# audio-interface.net
KiCad netlist of a schematic drawn in EAGLE
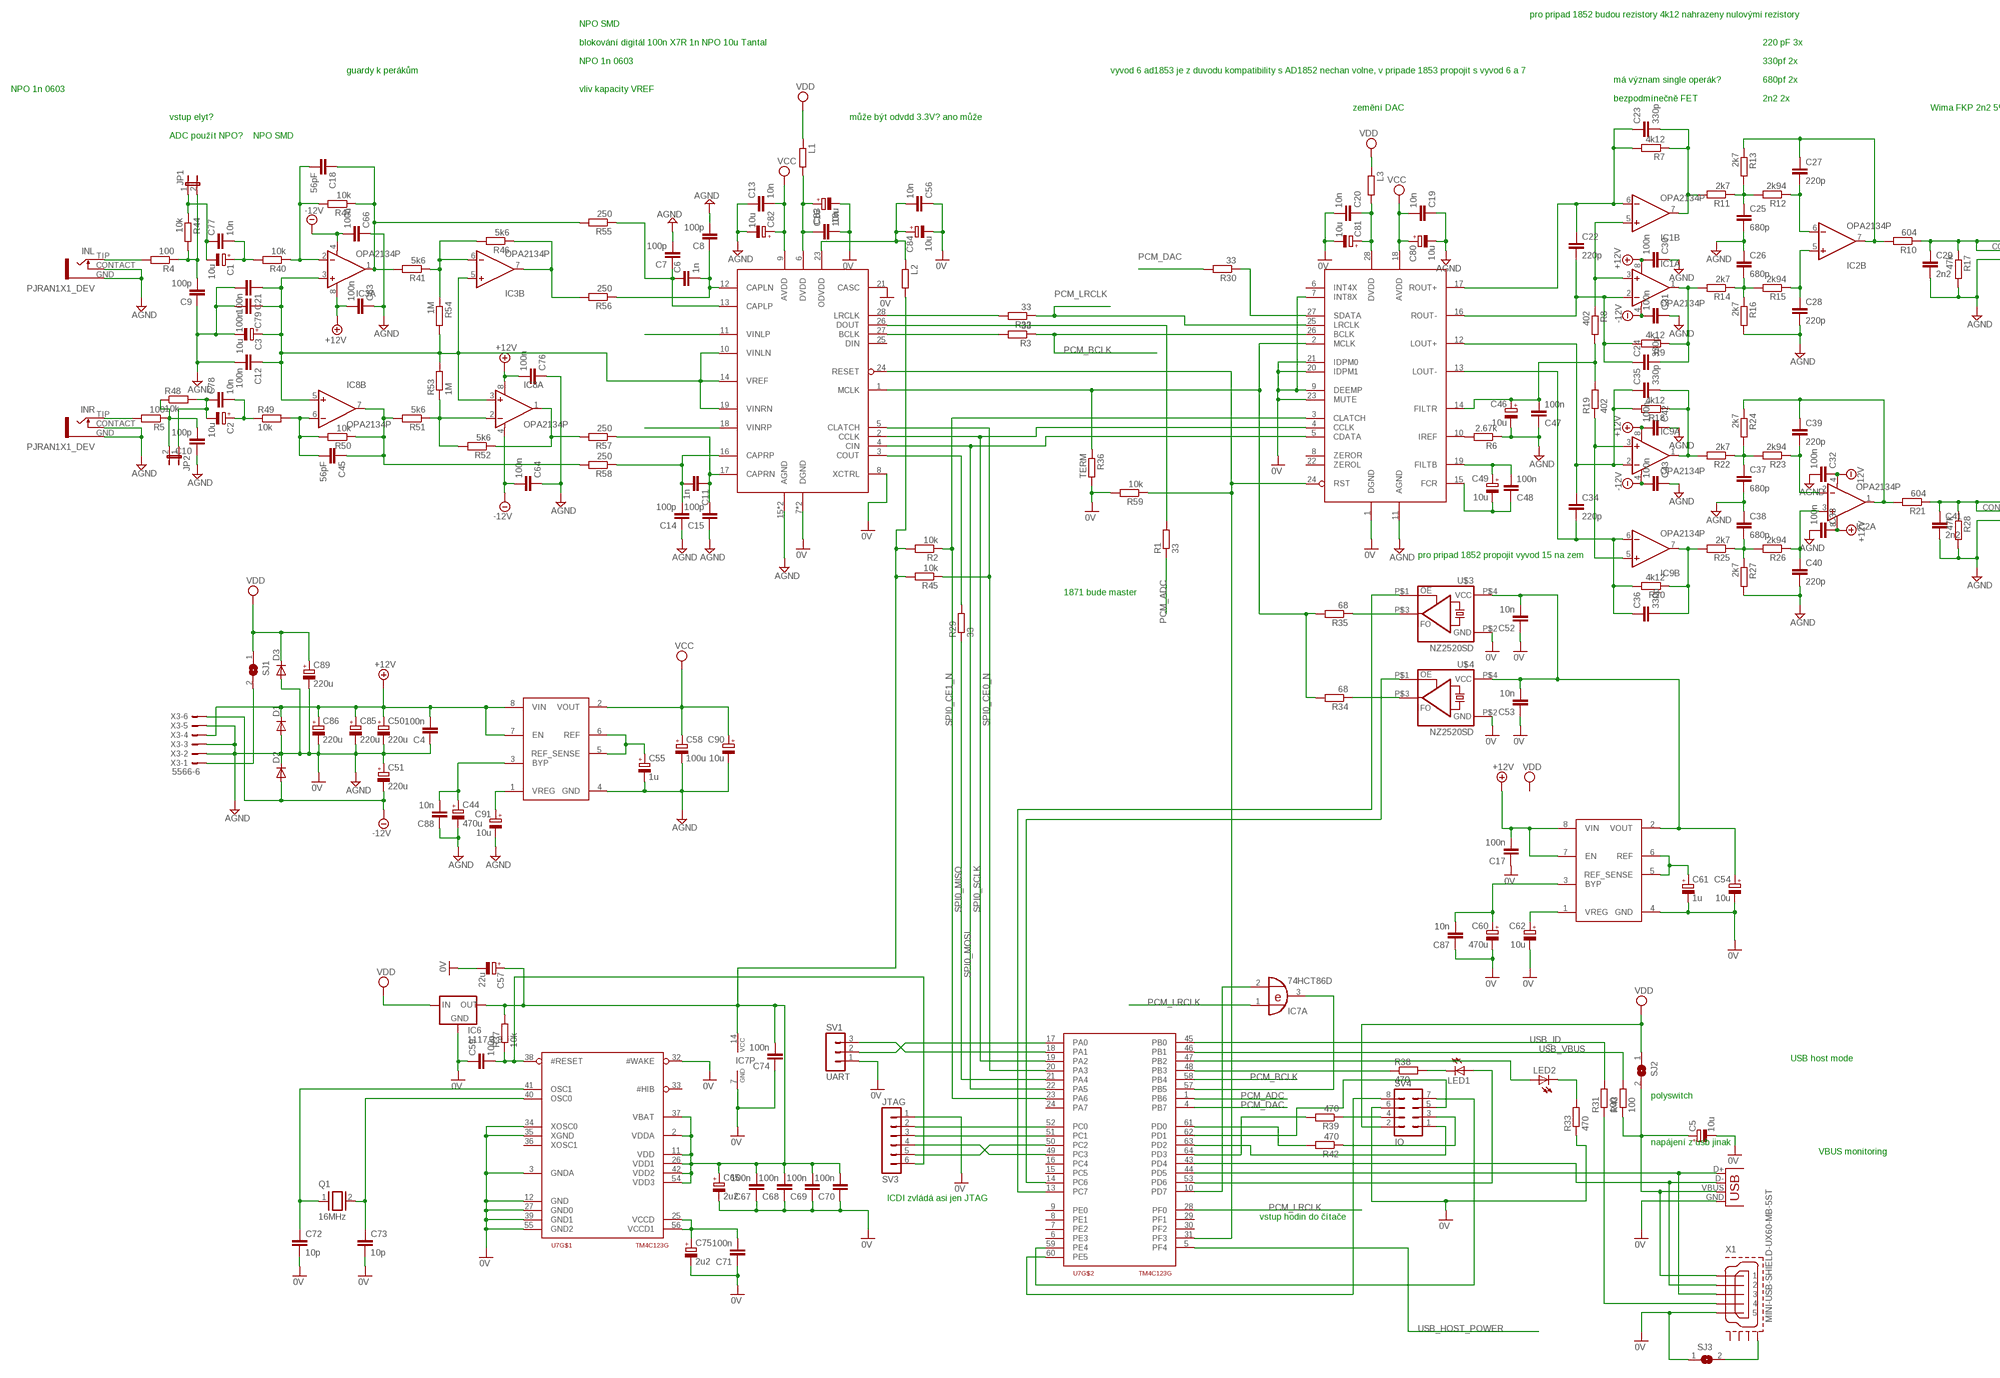
[diagram p0: schematic, sheet 1, part 1 of 2]
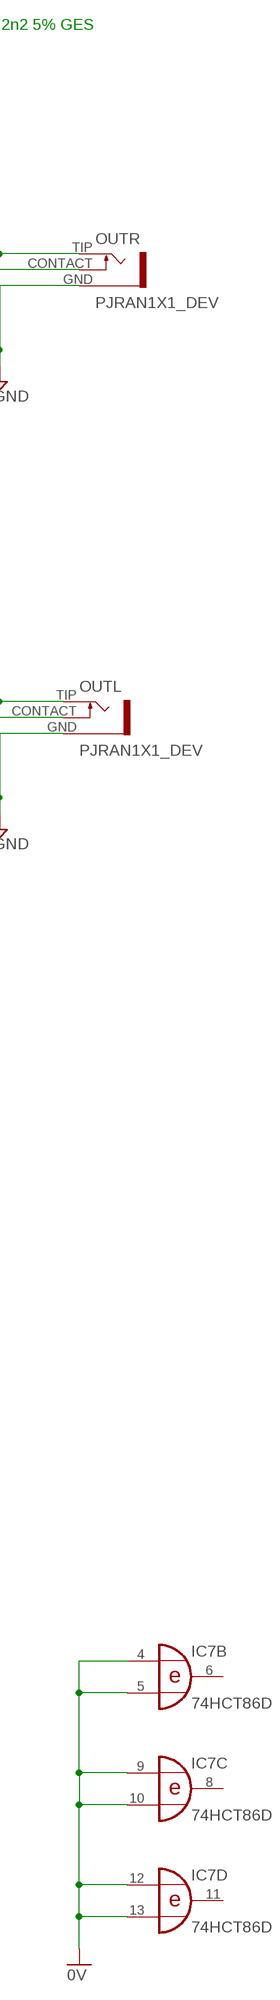
[diagram p1: schematic, sheet 1, part 2 of 2]

(export (version "E")
  (design (tool "Eeschema 10.0.6"))
  (components
    (comp (ref "C1")
      (value "10u")
      (footprint "eagle-import:E2,5-5")
      (libsource (lib "eagle-import") (part "CPOL-EUE2.5-5"))
    )
    (comp (ref "C2")
      (value "10u")
      (footprint "eagle-import:E2,5-5")
      (libsource (lib "eagle-import") (part "CPOL-EUE2.5-5"))
    )
    (comp (ref "C3")
      (value "10u")
      (footprint "eagle-import:E2,5-7")
      (libsource (lib "eagle-import") (part "CPOL-EUE2.5-7"))
    )
    (comp (ref "C4")
      (value "100n")
      (footprint "eagle-import:C0805")
      (libsource (lib "eagle-import") (part "C-EUC0805"))
    )
    (comp (ref "C5")
      (value "10u")
      (footprint "eagle-import:E2,5-7")
      (libsource (lib "eagle-import") (part "CPOL-EUE2.5-7"))
    )
    (comp (ref "C6")
      (value "1n")
      (footprint "eagle-import:C0805K")
      (libsource (lib "eagle-import") (part "C-EUC0805K"))
    )
    (comp (ref "C7")
      (value "100p")
      (footprint "eagle-import:C0805K")
      (libsource (lib "eagle-import") (part "C-EUC0805K"))
    )
    (comp (ref "C8")
      (value "100p")
      (footprint "eagle-import:C0805K")
      (libsource (lib "eagle-import") (part "C-EUC0805K"))
    )
    (comp (ref "C9")
      (value "100p")
      (footprint "eagle-import:C0805K")
      (libsource (lib "eagle-import") (part "C-EUC0805K"))
    )
    (comp (ref "C10")
      (value "100p")
      (footprint "eagle-import:C0805K")
      (libsource (lib "eagle-import") (part "C-EUC0805K"))
    )
    (comp (ref "C11")
      (value "1n")
      (footprint "eagle-import:C0805K")
      (libsource (lib "eagle-import") (part "C-EUC0805K"))
    )
    (comp (ref "C12")
      (value "100n")
      (footprint "eagle-import:C0805")
      (libsource (lib "eagle-import") (part "C-EUC0805"))
    )
    (comp (ref "C13")
      (value "10n")
      (footprint "eagle-import:C0805")
      (libsource (lib "eagle-import") (part "C-EUC0805"))
    )
    (comp (ref "C14")
      (value "100p")
      (footprint "eagle-import:C0805K")
      (libsource (lib "eagle-import") (part "C-EUC0805K"))
    )
    (comp (ref "C15")
      (value "100p")
      (footprint "eagle-import:C0805K")
      (libsource (lib "eagle-import") (part "C-EUC0805K"))
    )
    (comp (ref "C16")
      (value "10n")
      (footprint "eagle-import:C0805")
      (libsource (lib "eagle-import") (part "C-EUC0805"))
    )
    (comp (ref "C17")
      (value "100n")
      (footprint "eagle-import:C0805")
      (libsource (lib "eagle-import") (part "C-EUC0805"))
    )
    (comp (ref "C18")
      (value "56pF")
      (footprint "eagle-import:C0805K")
      (libsource (lib "eagle-import") (part "C-EUC0805K"))
    )
    (comp (ref "C19")
      (value "10n")
      (footprint "eagle-import:C0805")
      (libsource (lib "eagle-import") (part "C-EUC0805"))
    )
    (comp (ref "C20")
      (value "10n")
      (footprint "eagle-import:C0805")
      (libsource (lib "eagle-import") (part "C-EUC0805"))
    )
    (comp (ref "C21")
      (value "100n")
      (footprint "eagle-import:C0805")
      (libsource (lib "eagle-import") (part "C-EUC0805"))
    )
    (comp (ref "C22")
      (value "220p")
      (footprint "eagle-import:C0805K")
      (libsource (lib "eagle-import") (part "C-EUC0805K"))
    )
    (comp (ref "C23")
      (value "330p")
      (footprint "eagle-import:C0805K")
      (libsource (lib "eagle-import") (part "C-EUC0805K"))
    )
    (comp (ref "C24")
      (value "330p")
      (footprint "eagle-import:C0805K")
      (libsource (lib "eagle-import") (part "C-EUC0805K"))
    )
    (comp (ref "C25")
      (value "680p")
      (footprint "eagle-import:C050-050X075")
      (libsource (lib "eagle-import") (part "C-EU050-050X075"))
    )
    (comp (ref "C26")
      (value "680p")
      (footprint "eagle-import:C050-050X075")
      (libsource (lib "eagle-import") (part "C-EU050-050X075"))
    )
    (comp (ref "C27")
      (value "220p")
      (footprint "eagle-import:C0805K")
      (libsource (lib "eagle-import") (part "C-EUC0805K"))
    )
    (comp (ref "C28")
      (value "220p")
      (footprint "eagle-import:C0805K")
      (libsource (lib "eagle-import") (part "C-EUC0805K"))
    )
    (comp (ref "C29")
      (value "2n2")
      (footprint "eagle-import:C050-050X075")
      (libsource (lib "eagle-import") (part "C-EU050-050X075"))
    )
    (comp (ref "C30")
      (value "100n")
      (footprint "eagle-import:C0805")
      (libsource (lib "eagle-import") (part "C-EUC0805"))
    )
    (comp (ref "C31")
      (value "100n")
      (footprint "eagle-import:C0805")
      (libsource (lib "eagle-import") (part "C-EUC0805"))
    )
    (comp (ref "C32")
      (value "100n")
      (footprint "eagle-import:C0805")
      (libsource (lib "eagle-import") (part "C-EUC0805"))
    )
    (comp (ref "C33")
      (value "100n")
      (footprint "eagle-import:C0805")
      (libsource (lib "eagle-import") (part "C-EUC0805"))
    )
    (comp (ref "C34")
      (value "220p")
      (footprint "eagle-import:C0805K")
      (libsource (lib "eagle-import") (part "C-EUC0805K"))
    )
    (comp (ref "C35")
      (value "330p")
      (footprint "eagle-import:C0805K")
      (libsource (lib "eagle-import") (part "C-EUC0805K"))
    )
    (comp (ref "C36")
      (value "330p")
      (footprint "eagle-import:C0805K")
      (libsource (lib "eagle-import") (part "C-EUC0805K"))
    )
    (comp (ref "C37")
      (value "680p")
      (footprint "eagle-import:C050-050X075")
      (libsource (lib "eagle-import") (part "C-EU050-050X075"))
    )
    (comp (ref "C38")
      (value "680p")
      (footprint "eagle-import:C050-050X075")
      (libsource (lib "eagle-import") (part "C-EU050-050X075"))
    )
    (comp (ref "C39")
      (value "220p")
      (footprint "eagle-import:C0805K")
      (libsource (lib "eagle-import") (part "C-EUC0805K"))
    )
    (comp (ref "C40")
      (value "220p")
      (footprint "eagle-import:C0805K")
      (libsource (lib "eagle-import") (part "C-EUC0805K"))
    )
    (comp (ref "C41")
      (value "2n2")
      (footprint "eagle-import:C050-050X075")
      (libsource (lib "eagle-import") (part "C-EU050-050X075"))
    )
    (comp (ref "C42")
      (value "100n")
      (footprint "eagle-import:C0805")
      (libsource (lib "eagle-import") (part "C-EUC0805"))
    )
    (comp (ref "C43")
      (value "100n")
      (footprint "eagle-import:C0805")
      (libsource (lib "eagle-import") (part "C-EUC0805"))
    )
    (comp (ref "C44")
      (value "470u")
      (footprint "eagle-import:E2,5-7")
      (libsource (lib "eagle-import") (part "CPOL-EUE2.5-7"))
    )
    (comp (ref "C45")
      (value "56pF")
      (footprint "eagle-import:C0805K")
      (libsource (lib "eagle-import") (part "C-EUC0805K"))
    )
    (comp (ref "C46")
      (value "10u")
      (footprint "eagle-import:SMC_A")
      (libsource (lib "eagle-import") (part "CPOL-EUSMCA"))
    )
    (comp (ref "C47")
      (value "100n")
      (footprint "eagle-import:C0805")
      (libsource (lib "eagle-import") (part "C-EUC0805"))
    )
    (comp (ref "C48")
      (value "100n")
      (footprint "eagle-import:C0805")
      (libsource (lib "eagle-import") (part "C-EUC0805"))
    )
    (comp (ref "C49")
      (value "10u")
      (footprint "eagle-import:SMC_A")
      (libsource (lib "eagle-import") (part "CPOL-EUSMCA"))
    )
    (comp (ref "C50")
      (value "220u")
      (footprint "eagle-import:E2,5-7")
      (libsource (lib "eagle-import") (part "CPOL-EUE2.5-7"))
    )
    (comp (ref "C51")
      (value "220u")
      (footprint "eagle-import:E2,5-7")
      (libsource (lib "eagle-import") (part "CPOL-EUE2.5-7"))
    )
    (comp (ref "C52")
      (value "10n")
      (footprint "eagle-import:C0805")
      (libsource (lib "eagle-import") (part "C-EUC0805"))
    )
    (comp (ref "C53")
      (value "10n")
      (footprint "eagle-import:C0805")
      (libsource (lib "eagle-import") (part "C-EUC0805"))
    )
    (comp (ref "C54")
      (value "10u")
      (footprint "eagle-import:CT6032")
      (libsource (lib "eagle-import") (part "CPOL-EUCT6032"))
    )
    (comp (ref "C55")
      (value "1u")
      (footprint "eagle-import:CT3216")
      (libsource (lib "eagle-import") (part "CPOL-EUCT3216"))
    )
    (comp (ref "C56")
      (value "10n")
      (footprint "eagle-import:C0805")
      (libsource (lib "eagle-import") (part "C-EUC0805"))
    )
    (comp (ref "C57")
      (value "22u")
      (footprint "eagle-import:CT6032")
      (libsource (lib "eagle-import") (part "CPOL-EUCT6032"))
    )
    (comp (ref "C58")
      (value "100u")
      (footprint "eagle-import:E2,5-7")
      (libsource (lib "eagle-import") (part "CPOL-EUE2.5-7"))
    )
    (comp (ref "C59")
      (value "100n")
      (footprint "eagle-import:C0805")
      (libsource (lib "eagle-import") (part "C-EUC0805"))
    )
    (comp (ref "C60")
      (value "470u")
      (footprint "eagle-import:E2,5-7")
      (libsource (lib "eagle-import") (part "CPOL-EUE2.5-7"))
    )
    (comp (ref "C61")
      (value "1u")
      (footprint "eagle-import:CT3216")
      (libsource (lib "eagle-import") (part "CPOL-EUCT3216"))
    )
    (comp (ref "C62")
      (value "10u")
      (footprint "eagle-import:CT6032")
      (libsource (lib "eagle-import") (part "CPOL-EUCT6032"))
    )
    (comp (ref "C63")
      (value "100n")
      (footprint "eagle-import:C0805")
      (libsource (lib "eagle-import") (part "C-EUC0805"))
    )
    (comp (ref "C64")
      (value "100n")
      (footprint "eagle-import:C0805")
      (libsource (lib "eagle-import") (part "C-EUC0805"))
    )
    (comp (ref "C65")
      (value "2u2")
      (footprint "eagle-import:CT3216")
      (libsource (lib "eagle-import") (part "CPOL-EUCT3216"))
    )
    (comp (ref "C66")
      (value "100n")
      (footprint "eagle-import:C0805")
      (libsource (lib "eagle-import") (part "C-EUC0805"))
    )
    (comp (ref "C67")
      (value "100n")
      (footprint "eagle-import:C0805")
      (libsource (lib "eagle-import") (part "C-EUC0805"))
    )
    (comp (ref "C68")
      (value "100n")
      (footprint "eagle-import:C0805")
      (libsource (lib "eagle-import") (part "C-EUC0805"))
    )
    (comp (ref "C69")
      (value "100n")
      (footprint "eagle-import:C0805")
      (libsource (lib "eagle-import") (part "C-EUC0805"))
    )
    (comp (ref "C70")
      (value "100n")
      (footprint "eagle-import:C0805")
      (libsource (lib "eagle-import") (part "C-EUC0805"))
    )
    (comp (ref "C71")
      (value "100n")
      (footprint "eagle-import:C0805")
      (libsource (lib "eagle-import") (part "C-EUC0805"))
    )
    (comp (ref "C72")
      (value "10p")
      (footprint "eagle-import:C0805")
      (libsource (lib "eagle-import") (part "C-EUC0805"))
    )
    (comp (ref "C73")
      (value "10p")
      (footprint "eagle-import:C0805")
      (libsource (lib "eagle-import") (part "C-EUC0805"))
    )
    (comp (ref "C74")
      (value "100n")
      (footprint "eagle-import:C0805")
      (libsource (lib "eagle-import") (part "C-EUC0805"))
    )
    (comp (ref "C75")
      (value "2u2")
      (footprint "eagle-import:CT3216")
      (libsource (lib "eagle-import") (part "CPOL-EUCT3216"))
    )
    (comp (ref "C76")
      (value "100n")
      (footprint "eagle-import:C0805")
      (libsource (lib "eagle-import") (part "C-EUC0805"))
    )
    (comp (ref "C77")
      (value "10n")
      (footprint "eagle-import:C0805K")
      (libsource (lib "eagle-import") (part "C-EUC0805K"))
    )
    (comp (ref "C78")
      (value "10n")
      (footprint "eagle-import:C0805K")
      (libsource (lib "eagle-import") (part "C-EUC0805K"))
    )
    (comp (ref "C79")
      (value "100n")
      (footprint "eagle-import:C0805")
      (libsource (lib "eagle-import") (part "C-EUC0805"))
    )
    (comp (ref "C80")
      (value "10u")
      (footprint "eagle-import:SMC_A")
      (libsource (lib "eagle-import") (part "CPOL-EUSMCA"))
    )
    (comp (ref "C81")
      (value "10u")
      (footprint "eagle-import:SMC_A")
      (libsource (lib "eagle-import") (part "CPOL-EUSMCA"))
    )
    (comp (ref "C82")
      (value "10u")
      (footprint "eagle-import:SMC_A")
      (libsource (lib "eagle-import") (part "CPOL-EUSMCA"))
    )
    (comp (ref "C83")
      (value "10u")
      (footprint "eagle-import:SMC_A")
      (libsource (lib "eagle-import") (part "CPOL-EUSMCA"))
    )
    (comp (ref "C84")
      (value "10u")
      (footprint "eagle-import:SMC_A")
      (libsource (lib "eagle-import") (part "CPOL-EUSMCA"))
    )
    (comp (ref "C85")
      (value "220u")
      (footprint "eagle-import:E2,5-7")
      (libsource (lib "eagle-import") (part "CPOL-EUE2.5-7"))
    )
    (comp (ref "C86")
      (value "220u")
      (footprint "eagle-import:E2,5-7")
      (libsource (lib "eagle-import") (part "CPOL-EUE2.5-7"))
    )
    (comp (ref "C87")
      (value "10n")
      (footprint "eagle-import:C0805")
      (libsource (lib "eagle-import") (part "C-EUC0805"))
    )
    (comp (ref "C88")
      (value "10n")
      (footprint "eagle-import:C0805")
      (libsource (lib "eagle-import") (part "C-EUC0805"))
    )
    (comp (ref "C89")
      (value "220u")
      (footprint "eagle-import:E2,5-7")
      (libsource (lib "eagle-import") (part "CPOL-EUE2.5-7"))
    )
    (comp (ref "C90")
      (value "10u")
      (footprint "eagle-import:CT6032")
      (libsource (lib "eagle-import") (part "CPOL-EUCT6032"))
    )
    (comp (ref "C91")
      (value "10u")
      (footprint "eagle-import:CT6032")
      (libsource (lib "eagle-import") (part "CPOL-EUCT6032"))
    )
    (comp (ref "D1")
      (value "DIODE-MINIMELF")
      (footprint "eagle-import:MINIMELF")
      (libsource (lib "eagle-import") (part "DIODE-MINIMELF"))
    )
    (comp (ref "D2")
      (value "DIODE-MINIMELF")
      (footprint "eagle-import:MINIMELF")
      (libsource (lib "eagle-import") (part "DIODE-MINIMELF"))
    )
    (comp (ref "D3")
      (value "DIODE-MINIMELF")
      (footprint "eagle-import:MINIMELF")
      (libsource (lib "eagle-import") (part "DIODE-MINIMELF"))
    )
    (comp (ref "IC1")
      (value "OPA2134P")
      (footprint "eagle-import:DIL08")
      (fields
        (field (name "MF") "TEXAS INSTRUMENTS")
        (field (name "MPN") "OPA2134PA")
        (field (name "MF_1") "TEXAS INSTRUMENTS")
        (field (name "MPN_1") "OPA2134PA")
        (field (name "OC_FARNELL") "1097574")
        (field (name "OC_NEWARK") "74K3897")
      )
      (libsource (lib "eagle-import") (part "OPA2134P"))
    )
    (comp (ref "IC2")
      (value "OPA2134P")
      (footprint "eagle-import:DIL08")
      (fields (field (name "MF") "TEXAS INSTRUMENTS") (field (name "MPN") "OPA2134PA"))
      (libsource (lib "eagle-import") (part "OPA2134P"))
    )
    (comp (ref "IC3")
      (value "OPA2134P")
      (footprint "eagle-import:DIL08")
      (fields
        (field (name "MF") "TEXAS INSTRUMENTS")
        (field (name "MPN") "OPA2134PA")
        (field (name "MF_1") "TEXAS INSTRUMENTS")
        (field (name "MPN_1") "OPA2134PA")
        (field (name "OC_FARNELL") "1097574")
        (field (name "OC_NEWARK") "74K3897")
      )
      (libsource (lib "eagle-import") (part "OPA2134P"))
    )
    (comp (ref "IC6")
      (value "1117 3.3")
      (footprint "eagle-import:SOT223")
      (libsource (lib "eagle-import") (part "LM1117"))
    )
    (comp (ref "IC7")
      (value "74HCT86D")
      (footprint "eagle-import:SO14")
      (libsource (lib "eagle-import") (part "7486DHCT"))
    )
    (comp (ref "IC8")
      (value "OPA2134P")
      (footprint "eagle-import:DIL08")
      (fields
        (field (name "MF") "TEXAS INSTRUMENTS")
        (field (name "MPN") "OPA2134PA")
        (field (name "MF_1") "TEXAS INSTRUMENTS")
        (field (name "MPN_1") "OPA2134PA")
        (field (name "OC_FARNELL") "1097574")
        (field (name "OC_NEWARK") "74K3897")
      )
      (libsource (lib "eagle-import") (part "OPA2134P"))
    )
    (comp (ref "IC9")
      (value "OPA2134P")
      (footprint "eagle-import:DIL08")
      (fields
        (field (name "MF") "TEXAS INSTRUMENTS")
        (field (name "MPN") "OPA2134PA")
        (field (name "MF_1") "TEXAS INSTRUMENTS")
        (field (name "MPN_1") "OPA2134PA")
        (field (name "OC_FARNELL") "1097574")
        (field (name "OC_NEWARK") "74K3897")
      )
      (libsource (lib "eagle-import") (part "OPA2134P"))
    )
    (comp (ref "INL")
      (value "PJRAN1X1_DEV")
      (footprint "eagle-import:PJRAN1X1")
      (libsource (lib "eagle-import") (part "PJRAN1X1_DEV"))
    )
    (comp (ref "INR")
      (value "PJRAN1X1_DEV")
      (footprint "eagle-import:PJRAN1X1")
      (libsource (lib "eagle-import") (part "PJRAN1X1_DEV"))
    )
    (comp (ref "JP1")
      (value "JP1E")
      (footprint "eagle-import:JP1")
      (libsource (lib "eagle-import") (part "JP1E"))
    )
    (comp (ref "JP2")
      (value "JP1E")
      (footprint "eagle-import:JP1")
      (libsource (lib "eagle-import") (part "JP1E"))
    )
    (comp (ref "L1")
      (value "R-EU_R0805")
      (footprint "eagle-import:R0805")
      (libsource (lib "eagle-import") (part "R-EU_R0805"))
    )
    (comp (ref "L2")
      (value "R-EU_R0805")
      (footprint "eagle-import:R0805")
      (libsource (lib "eagle-import") (part "R-EU_R0805"))
    )
    (comp (ref "L3")
      (value "R-EU_R0805")
      (footprint "eagle-import:R0805")
      (libsource (lib "eagle-import") (part "R-EU_R0805"))
    )
    (comp (ref "LED1")
      (value "LED3MM")
      (footprint "eagle-import:LED3MM")
      (libsource (lib "eagle-import") (part "LED3MM"))
    )
    (comp (ref "LED2")
      (value "LED3MM")
      (footprint "eagle-import:LED3MM")
      (libsource (lib "eagle-import") (part "LED3MM"))
    )
    (comp (ref "OUTL")
      (value "PJRAN1X1_DEV")
      (footprint "eagle-import:PJRAN1X1")
      (libsource (lib "eagle-import") (part "PJRAN1X1_DEV"))
    )
    (comp (ref "OUTR")
      (value "PJRAN1X1_DEV")
      (footprint "eagle-import:PJRAN1X1")
      (libsource (lib "eagle-import") (part "PJRAN1X1_DEV"))
    )
    (comp (ref "Q1")
      (value "16MHz")
      (footprint "eagle-import:QS")
      (libsource (lib "eagle-import") (part "XTAL/S"))
    )
    (comp (ref "R1")
      (value "33")
      (footprint "eagle-import:R0805")
      (libsource (lib "eagle-import") (part "R-EU_R0805"))
    )
    (comp (ref "R2")
      (value "10k")
      (footprint "eagle-import:R0805")
      (libsource (lib "eagle-import") (part "R-EU_R0805"))
    )
    (comp (ref "R3")
      (value "33")
      (footprint "eagle-import:R0805")
      (libsource (lib "eagle-import") (part "R-EU_R0805"))
    )
    (comp (ref "R4")
      (value "100")
      (footprint "eagle-import:M0805")
      (libsource (lib "eagle-import") (part "R-EU_M0805"))
    )
    (comp (ref "R5")
      (value "100")
      (footprint "eagle-import:M0805")
      (libsource (lib "eagle-import") (part "R-EU_M0805"))
    )
    (comp (ref "R6")
      (value "2.67k")
      (footprint "eagle-import:M1406")
      (libsource (lib "eagle-import") (part "R-EU_M1406"))
    )
    (comp (ref "R7")
      (value "4k12")
      (footprint "eagle-import:M1206")
      (libsource (lib "eagle-import") (part "R-EU_M1206"))
    )
    (comp (ref "R8")
      (value "402")
      (footprint "eagle-import:M1206")
      (libsource (lib "eagle-import") (part "R-EU_M1206"))
    )
    (comp (ref "R9")
      (value "4k12")
      (footprint "eagle-import:M1206")
      (libsource (lib "eagle-import") (part "R-EU_M1206"))
    )
    (comp (ref "R10")
      (value "604")
      (footprint "eagle-import:M1206")
      (libsource (lib "eagle-import") (part "R-EU_M1206"))
    )
    (comp (ref "R11")
      (value "2k7")
      (footprint "eagle-import:M1206")
      (libsource (lib "eagle-import") (part "R-EU_M1206"))
    )
    (comp (ref "R12")
      (value "2k94")
      (footprint "eagle-import:M1206")
      (libsource (lib "eagle-import") (part "R-EU_M1206"))
    )
    (comp (ref "R13")
      (value "2k7")
      (footprint "eagle-import:M1206")
      (libsource (lib "eagle-import") (part "R-EU_M1206"))
    )
    (comp (ref "R14")
      (value "2k7")
      (footprint "eagle-import:M1206")
      (libsource (lib "eagle-import") (part "R-EU_M1206"))
    )
    (comp (ref "R15")
      (value "2k94")
      (footprint "eagle-import:M1206")
      (libsource (lib "eagle-import") (part "R-EU_M1206"))
    )
    (comp (ref "R16")
      (value "2k7")
      (footprint "eagle-import:M1206")
      (libsource (lib "eagle-import") (part "R-EU_M1206"))
    )
    (comp (ref "R17")
      (value "47k")
      (footprint "eagle-import:M1206")
      (libsource (lib "eagle-import") (part "R-EU_M1206"))
    )
    (comp (ref "R18")
      (value "4k12")
      (footprint "eagle-import:M1206")
      (libsource (lib "eagle-import") (part "R-EU_M1206"))
    )
    (comp (ref "R19")
      (value "402")
      (footprint "eagle-import:M1206")
      (libsource (lib "eagle-import") (part "R-EU_M1206"))
    )
    (comp (ref "R20")
      (value "4k12")
      (footprint "eagle-import:M1206")
      (libsource (lib "eagle-import") (part "R-EU_M1206"))
    )
    (comp (ref "R21")
      (value "604")
      (footprint "eagle-import:M1206")
      (libsource (lib "eagle-import") (part "R-EU_M1206"))
    )
    (comp (ref "R22")
      (value "2k7")
      (footprint "eagle-import:M1206")
      (libsource (lib "eagle-import") (part "R-EU_M1206"))
    )
    (comp (ref "R23")
      (value "2k94")
      (footprint "eagle-import:M1206")
      (libsource (lib "eagle-import") (part "R-EU_M1206"))
    )
    (comp (ref "R24")
      (value "2k7")
      (footprint "eagle-import:M1206")
      (libsource (lib "eagle-import") (part "R-EU_M1206"))
    )
    (comp (ref "R25")
      (value "2k7")
      (footprint "eagle-import:M1206")
      (libsource (lib "eagle-import") (part "R-EU_M1206"))
    )
    (comp (ref "R26")
      (value "2k94")
      (footprint "eagle-import:M1206")
      (libsource (lib "eagle-import") (part "R-EU_M1206"))
    )
    (comp (ref "R27")
      (value "2k7")
      (footprint "eagle-import:M1206")
      (libsource (lib "eagle-import") (part "R-EU_M1206"))
    )
    (comp (ref "R28")
      (value "47k")
      (footprint "eagle-import:M1206")
      (libsource (lib "eagle-import") (part "R-EU_M1206"))
    )
    (comp (ref "R29")
      (value "33")
      (footprint "eagle-import:R0805")
      (libsource (lib "eagle-import") (part "R-EU_R0805"))
    )
    (comp (ref "R30")
      (value "33")
      (footprint "eagle-import:R0805")
      (libsource (lib "eagle-import") (part "R-EU_R0805"))
    )
    (comp (ref "R31")
      (value "100")
      (footprint "eagle-import:R0805")
      (libsource (lib "eagle-import") (part "R-EU_R0805"))
    )
    (comp (ref "R32")
      (value "33")
      (footprint "eagle-import:R0805")
      (libsource (lib "eagle-import") (part "R-EU_R0805"))
    )
    (comp (ref "R33")
      (value "470")
      (footprint "eagle-import:R0805")
      (libsource (lib "eagle-import") (part "R-EU_R0805"))
    )
    (comp (ref "R34")
      (value "68")
      (footprint "eagle-import:M1206")
      (libsource (lib "eagle-import") (part "R-EU_M1206"))
    )
    (comp (ref "R35")
      (value "68")
      (footprint "eagle-import:M1206")
      (libsource (lib "eagle-import") (part "R-EU_M1206"))
    )
    (comp (ref "R36")
      (value "TERM")
      (footprint "eagle-import:R0805")
      (libsource (lib "eagle-import") (part "R-EU_R0805"))
    )
    (comp (ref "R37")
      (value "10k")
      (footprint "eagle-import:R0805")
      (libsource (lib "eagle-import") (part "R-EU_R0805"))
    )
    (comp (ref "R38")
      (value "470")
      (footprint "eagle-import:R0805")
      (libsource (lib "eagle-import") (part "R-EU_R0805"))
    )
    (comp (ref "R39")
      (value "470")
      (footprint "eagle-import:R0805")
      (libsource (lib "eagle-import") (part "R-EU_R0805"))
    )
    (comp (ref "R40")
      (value "10k")
      (footprint "eagle-import:M1206")
      (libsource (lib "eagle-import") (part "R-EU_M1206"))
    )
    (comp (ref "R41")
      (value "5k6")
      (footprint "eagle-import:M1206")
      (libsource (lib "eagle-import") (part "R-EU_M1206"))
    )
    (comp (ref "R42")
      (value "470")
      (footprint "eagle-import:R0805")
      (libsource (lib "eagle-import") (part "R-EU_R0805"))
    )
    (comp (ref "R43")
      (value "100")
      (footprint "eagle-import:R0805")
      (libsource (lib "eagle-import") (part "R-EU_R0805"))
    )
    (comp (ref "R44")
      (value "10k")
      (footprint "eagle-import:M1206")
      (libsource (lib "eagle-import") (part "R-EU_M1206"))
    )
    (comp (ref "R45")
      (value "10k")
      (footprint "eagle-import:R0805")
      (libsource (lib "eagle-import") (part "R-EU_R0805"))
    )
    (comp (ref "R46")
      (value "5k6")
      (footprint "eagle-import:M1206")
      (libsource (lib "eagle-import") (part "R-EU_M1206"))
    )
    (comp (ref "R47")
      (value "10k")
      (footprint "eagle-import:M1206")
      (libsource (lib "eagle-import") (part "R-EU_M1206"))
    )
    (comp (ref "R48")
      (value "10k")
      (footprint "eagle-import:M1206")
      (libsource (lib "eagle-import") (part "R-EU_M1206"))
    )
    (comp (ref "R49")
      (value "10k")
      (footprint "eagle-import:M1206")
      (libsource (lib "eagle-import") (part "R-EU_M1206"))
    )
    (comp (ref "R50")
      (value "10k")
      (footprint "eagle-import:M1206")
      (libsource (lib "eagle-import") (part "R-EU_M1206"))
    )
    (comp (ref "R51")
      (value "5k6")
      (footprint "eagle-import:M1206")
      (libsource (lib "eagle-import") (part "R-EU_M1206"))
    )
    (comp (ref "R52")
      (value "5k6")
      (footprint "eagle-import:M1206")
      (libsource (lib "eagle-import") (part "R-EU_M1206"))
    )
    (comp (ref "R53")
      (value "1M")
      (footprint "eagle-import:M1206")
      (libsource (lib "eagle-import") (part "R-EU_M1206"))
    )
    (comp (ref "R54")
      (value "1M")
      (footprint "eagle-import:M1206")
      (libsource (lib "eagle-import") (part "R-EU_M1206"))
    )
    (comp (ref "R55")
      (value "250")
      (footprint "eagle-import:M1206")
      (libsource (lib "eagle-import") (part "R-EU_M1206"))
    )
    (comp (ref "R56")
      (value "250")
      (footprint "eagle-import:M1206")
      (libsource (lib "eagle-import") (part "R-EU_M1206"))
    )
    (comp (ref "R57")
      (value "250")
      (footprint "eagle-import:M1206")
      (libsource (lib "eagle-import") (part "R-EU_M1206"))
    )
    (comp (ref "R58")
      (value "250")
      (footprint "eagle-import:M1206")
      (libsource (lib "eagle-import") (part "R-EU_M1206"))
    )
    (comp (ref "R59")
      (value "10k")
      (footprint "eagle-import:R0805")
      (libsource (lib "eagle-import") (part "R-EU_R0805"))
    )
    (comp (ref "SJ1") (value "SJ") (footprint "eagle-import:SJ") (libsource (lib "eagle-import") (part "SJ")))
    (comp (ref "SJ2") (value "SJ") (footprint "eagle-import:SJ") (libsource (lib "eagle-import") (part "SJ")))
    (comp (ref "SJ3") (value "SJ") (footprint "eagle-import:SJ") (libsource (lib "eagle-import") (part "SJ")))
    (comp (ref "SV1")
      (value "UART")
      (footprint "eagle-import:MA03-1")
      (libsource (lib "eagle-import") (part "MA03-1"))
    )
    (comp (ref "SV3")
      (value "JTAG")
      (footprint "eagle-import:MA06-1")
      (libsource (lib "eagle-import") (part "MA06-1"))
    )
    (comp (ref "SV4")
      (value "IO")
      (footprint "eagle-import:MA04-2")
      (libsource (lib "eagle-import") (part "MA04-2"))
    )
    (comp (ref "U$3")
      (value "NZ2520SD")
      (footprint "eagle-import:OSC2X2.5")
      (libsource (lib "eagle-import") (part "OSC-3ST"))
    )
    (comp (ref "U$4")
      (value "NZ2520SD")
      (footprint "eagle-import:OSC2X2.5")
      (libsource (lib "eagle-import") (part "OSC-3ST"))
    )
    (comp (ref "U1")
      (value "AD1853")
      (footprint "eagle-import:SSOP-28")
      (libsource (lib "eagle-import") (part "AD1853"))
    )
    (comp (ref "U2")
      (value "AD1871")
      (footprint "eagle-import:SSOP-28")
      (libsource (lib "eagle-import") (part "AD1871"))
    )
    (comp (ref "U5")
      (value "ADM7150")
      (footprint "eagle-import:SO8-COOL")
      (libsource (lib "eagle-import") (part "ADM7150"))
    )
    (comp (ref "U6")
      (value "ADM7150")
      (footprint "eagle-import:SO8-COOL")
      (libsource (lib "eagle-import") (part "ADM7150"))
    )
    (comp (ref "U7")
      (value "TM4C123G")
      (footprint "eagle-import:LQFP64")
      (libsource (lib "eagle-import") (part "TM4C123G"))
    )
    (comp (ref "X1")
      (value "MINI-USB-SHIELD-UX60-MB-5ST")
      (footprint "eagle-import:UX60-MB-5ST")
      (libsource (lib "eagle-import") (part "MINI-USB-SHIELD-UX60-MB-5ST"))
    )
    (comp (ref "X3")
      (value "5566-6")
      (footprint "eagle-import:5566-6")
      (fields (field (name "MPN") "95566-61002"))
      (libsource (lib "eagle-import") (part "5566-6"))
    )
    (comp (ref "X7")
      (value "USB-B-H")
      (footprint "eagle-import:USB-B-H")
      (libsource (lib "eagle-import") (part "USB-B-H"))
    )
  )
  (nets
    (net (code "1") (name "+12V") (class "Default")
      (node (ref "C17") (pin "2") (pinfunction "2_2") (pintype "passive"))
      (node (ref "C30") (pin "2") (pinfunction "2_2") (pintype "passive"))
      (node (ref "C33") (pin "1") (pinfunction "1_1") (pintype "passive"))
      (node (ref "C4") (pin "2") (pinfunction "2_2") (pintype "passive"))
      (node (ref "C42") (pin "2") (pinfunction "2_2") (pintype "passive"))
      (node (ref "C50") (pin "+") (pinfunction "+_+") (pintype "passive"))
      (node (ref "C63") (pin "2") (pinfunction "2_2") (pintype "passive"))
      (node (ref "C76") (pin "2") (pinfunction "2_2") (pintype "passive"))
      (node (ref "C85") (pin "+") (pinfunction "+_+") (pintype "passive"))
      (node (ref "C86") (pin "+") (pinfunction "+_+") (pintype "passive"))
      (node (ref "D1") (pin "C") (pinfunction "C_C") (pintype "passive"))
      (node (ref "IC1") (pin "8") (pinfunction "V+_8") (pintype "power_in"))
      (node (ref "IC2") (pin "8") (pinfunction "V+_8") (pintype "power_in"))
      (node (ref "IC3") (pin "8") (pinfunction "V+_8") (pintype "power_in"))
      (node (ref "IC8") (pin "8") (pinfunction "V+_8") (pintype "power_in"))
      (node (ref "IC9") (pin "8") (pinfunction "V+_8") (pintype "power_in"))
      (node (ref "U5") (pin "7") (pinfunction "EN_7") (pintype "bidirectional"))
      (node (ref "U5") (pin "8") (pinfunction "VIN_8") (pintype "bidirectional"))
      (node (ref "U6") (pin "7") (pinfunction "EN_7") (pintype "bidirectional"))
      (node (ref "U6") (pin "8") (pinfunction "VIN_8") (pintype "bidirectional"))
      (node (ref "X3") (pin "4") (pinfunction "S_4") (pintype "passive"))
    )
    (net (code "2") (name "-12V") (class "Default")
      (node (ref "C31") (pin "2") (pinfunction "2_2") (pintype "passive"))
      (node (ref "C32") (pin "1") (pinfunction "1_1") (pintype "passive"))
      (node (ref "C43") (pin "2") (pinfunction "2_2") (pintype "passive"))
      (node (ref "C51") (pin "-") (pinfunction "-_-") (pintype "passive"))
      (node (ref "C64") (pin "2") (pinfunction "2_2") (pintype "passive"))
      (node (ref "C66") (pin "2") (pinfunction "2_2") (pintype "passive"))
      (node (ref "D2") (pin "A") (pinfunction "A_A") (pintype "passive"))
      (node (ref "IC1") (pin "4") (pinfunction "V-_4") (pintype "power_in"))
      (node (ref "IC2") (pin "4") (pinfunction "V-_4") (pintype "power_in"))
      (node (ref "IC3") (pin "4") (pinfunction "V-_4") (pintype "power_in"))
      (node (ref "IC8") (pin "4") (pinfunction "V-_4") (pintype "power_in"))
      (node (ref "IC9") (pin "4") (pinfunction "V-_4") (pintype "power_in"))
      (node (ref "X3") (pin "6") (pinfunction "S_6") (pintype "passive"))
    )
    (net (code "3") (name "/PCM_ADC") (class "Default")
      (node (ref "R1") (pin "1") (pinfunction "1_1") (pintype "passive"))
      (node (ref "U7") (pin "1") (pinfunction "PB6_1") (pintype "bidirectional"))
    )
    (net (code "4") (name "/PCM_BCLK") (class "Default")
      (node (ref "R3") (pin "1") (pinfunction "1_1") (pintype "passive"))
      (node (ref "U1") (pin "26") (pinfunction "BCLK_26") (pintype "bidirectional"))
      (node (ref "U7") (pin "58") (pinfunction "PB4_58") (pintype "bidirectional"))
    )
    (net (code "5") (name "/PCM_DAC") (class "Default")
      (node (ref "R30") (pin "2") (pinfunction "2_2") (pintype "passive"))
      (node (ref "U7") (pin "4") (pinfunction "PB7_4") (pintype "bidirectional"))
    )
    (net (code "6") (name "/PCM_LRCLK") (class "Default")
      (node (ref "IC7") (pin "1") (pinfunction "I0_1") (pintype "input"))
      (node (ref "R32") (pin "1") (pinfunction "1_1") (pintype "passive"))
      (node (ref "U1") (pin "25") (pinfunction "LRCLK_25") (pintype "bidirectional"))
      (node (ref "U7") (pin "28") (pinfunction "PF0_28") (pintype "bidirectional"))
    )
    (net (code "7") (name "/SPI0_CE0_N") (class "Default")
      (node (ref "R45") (pin "1") (pinfunction "1_1") (pintype "passive"))
      (node (ref "U2") (pin "5") (pinfunction "CLATCH_5") (pintype "bidirectional"))
      (node (ref "U7") (pin "20") (pinfunction "PA3_20") (pintype "bidirectional"))
    )
    (net (code "8") (name "/SPI0_CE1_N") (class "Default")
      (node (ref "R2") (pin "1") (pinfunction "1_1") (pintype "passive"))
      (node (ref "U1") (pin "3") (pinfunction "CLATCH_3") (pintype "bidirectional"))
      (node (ref "U7") (pin "23") (pinfunction "PA6_23") (pintype "bidirectional"))
    )
    (net (code "9") (name "/SPI0_MISO") (class "Default")
      (node (ref "R29") (pin "1") (pinfunction "1_1") (pintype "passive"))
      (node (ref "U7") (pin "21") (pinfunction "PA4_21") (pintype "bidirectional"))
    )
    (net (code "10") (name "/SPI0_MOSI") (class "Default")
      (node (ref "U1") (pin "5") (pinfunction "CDATA_5") (pintype "bidirectional"))
      (node (ref "U2") (pin "4") (pinfunction "CIN_4") (pintype "bidirectional"))
      (node (ref "U7") (pin "22") (pinfunction "PA5_22") (pintype "bidirectional"))
    )
    (net (code "11") (name "/SPI0_SCLK") (class "Default")
      (node (ref "U1") (pin "4") (pinfunction "CCLK_4") (pintype "bidirectional"))
      (node (ref "U2") (pin "2") (pinfunction "CCLK_2") (pintype "bidirectional"))
      (node (ref "U7") (pin "19") (pinfunction "PA2_19") (pintype "bidirectional"))
    )
    (net (code "12") (name "/USB_HOST_POWER") (class "Default")
      (node (ref "U7") (pin "5") (pinfunction "PF4_5") (pintype "bidirectional"))
    )
    (net (code "13") (name "/USB_ID") (class "Default")
      (node (ref "R31") (pin "2") (pinfunction "2_2") (pintype "passive"))
      (node (ref "U7") (pin "45") (pinfunction "PB0_45") (pintype "bidirectional"))
    )
    (net (code "14") (name "/USB_VBUS") (class "Default")
      (node (ref "R43") (pin "2") (pinfunction "2_2") (pintype "passive"))
      (node (ref "U7") (pin "46") (pinfunction "PB1_46") (pintype "bidirectional"))
    )
    (net (code "15") (name "0V") (class "Default")
      (node (ref "C10") (pin "1") (pinfunction "1_1") (pintype "passive"))
      (node (ref "C12") (pin "2") (pinfunction "2_2") (pintype "passive"))
      (node (ref "C13") (pin "1") (pinfunction "1_1") (pintype "passive"))
      (node (ref "C14") (pin "1") (pinfunction "1_1") (pintype "passive"))
      (node (ref "C15") (pin "1") (pinfunction "1_1") (pintype "passive"))
      (node (ref "C16") (pin "2") (pinfunction "2_2") (pintype "passive"))
      (node (ref "C17") (pin "1") (pinfunction "1_1") (pintype "passive"))
      (node (ref "C19") (pin "1") (pinfunction "1_1") (pintype "passive"))
      (node (ref "C20") (pin "2") (pinfunction "2_2") (pintype "passive"))
      (node (ref "C21") (pin "2") (pinfunction "2_2") (pintype "passive"))
      (node (ref "C25") (pin "2") (pinfunction "2_2") (pintype "passive"))
      (node (ref "C26") (pin "1") (pinfunction "1_1") (pintype "passive"))
      (node (ref "C28") (pin "2") (pinfunction "2_2") (pintype "passive"))
      (node (ref "C29") (pin "2") (pinfunction "2_2") (pintype "passive"))
      (node (ref "C3") (pin "-") (pinfunction "-_-") (pintype "passive"))
      (node (ref "C30") (pin "1") (pinfunction "1_1") (pintype "passive"))
      (node (ref "C31") (pin "1") (pinfunction "1_1") (pintype "passive"))
      (node (ref "C32") (pin "2") (pinfunction "2_2") (pintype "passive"))
      (node (ref "C33") (pin "2") (pinfunction "2_2") (pintype "passive"))
      (node (ref "C37") (pin "2") (pinfunction "2_2") (pintype "passive"))
      (node (ref "C38") (pin "1") (pinfunction "1_1") (pintype "passive"))
      (node (ref "C4") (pin "1") (pinfunction "1_1") (pintype "passive"))
      (node (ref "C40") (pin "2") (pinfunction "2_2") (pintype "passive"))
      (node (ref "C41") (pin "2") (pinfunction "2_2") (pintype "passive"))
      (node (ref "C42") (pin "1") (pinfunction "1_1") (pintype "passive"))
      (node (ref "C43") (pin "1") (pinfunction "1_1") (pintype "passive"))
      (node (ref "C44") (pin "-") (pinfunction "-_-") (pintype "passive"))
      (node (ref "C46") (pin "-") (pinfunction "-_-") (pintype "passive"))
      (node (ref "C47") (pin "1") (pinfunction "1_1") (pintype "passive"))
      (node (ref "C5") (pin "-") (pinfunction "-_-") (pintype "passive"))
      (node (ref "C50") (pin "-") (pinfunction "-_-") (pintype "passive"))
      (node (ref "C51") (pin "+") (pinfunction "+_+") (pintype "passive"))
      (node (ref "C52") (pin "1") (pinfunction "1_1") (pintype "passive"))
      (node (ref "C53") (pin "1") (pinfunction "1_1") (pintype "passive"))
      (node (ref "C54") (pin "-") (pinfunction "-_-") (pintype "passive"))
      (node (ref "C55") (pin "-") (pinfunction "-_-") (pintype "passive"))
      (node (ref "C56") (pin "1") (pinfunction "1_1") (pintype "passive"))
      (node (ref "C57") (pin "-") (pinfunction "-_-") (pintype "passive"))
      (node (ref "C58") (pin "-") (pinfunction "-_-") (pintype "passive"))
      (node (ref "C59") (pin "1") (pinfunction "1_1") (pintype "passive"))
      (node (ref "C60") (pin "-") (pinfunction "-_-") (pintype "passive"))
      (node (ref "C61") (pin "-") (pinfunction "-_-") (pintype "passive"))
      (node (ref "C62") (pin "-") (pinfunction "-_-") (pintype "passive"))
      (node (ref "C63") (pin "1") (pinfunction "1_1") (pintype "passive"))
      (node (ref "C64") (pin "1") (pinfunction "1_1") (pintype "passive"))
      (node (ref "C65") (pin "-") (pinfunction "-_-") (pintype "passive"))
      (node (ref "C66") (pin "1") (pinfunction "1_1") (pintype "passive"))
      (node (ref "C67") (pin "1") (pinfunction "1_1") (pintype "passive"))
      (node (ref "C68") (pin "1") (pinfunction "1_1") (pintype "passive"))
      (node (ref "C69") (pin "1") (pinfunction "1_1") (pintype "passive"))
      (node (ref "C7") (pin "2") (pinfunction "2_2") (pintype "passive"))
      (node (ref "C70") (pin "1") (pinfunction "1_1") (pintype "passive"))
      (node (ref "C71") (pin "1") (pinfunction "1_1") (pintype "passive"))
      (node (ref "C72") (pin "2") (pinfunction "2_2") (pintype "passive"))
      (node (ref "C73") (pin "2") (pinfunction "2_2") (pintype "passive"))
      (node (ref "C74") (pin "1") (pinfunction "1_1") (pintype "passive"))
      (node (ref "C75") (pin "-") (pinfunction "-_-") (pintype "passive"))
      (node (ref "C76") (pin "1") (pinfunction "1_1") (pintype "passive"))
      (node (ref "C79") (pin "2") (pinfunction "2_2") (pintype "passive"))
      (node (ref "C8") (pin "2") (pinfunction "2_2") (pintype "passive"))
      (node (ref "C80") (pin "-") (pinfunction "-_-") (pintype "passive"))
      (node (ref "C81") (pin "-") (pinfunction "-_-") (pintype "passive"))
      (node (ref "C82") (pin "-") (pinfunction "-_-") (pintype "passive"))
      (node (ref "C83") (pin "-") (pinfunction "-_-") (pintype "passive"))
      (node (ref "C84") (pin "-") (pinfunction "-_-") (pintype "passive"))
      (node (ref "C85") (pin "-") (pinfunction "-_-") (pintype "passive"))
      (node (ref "C86") (pin "-") (pinfunction "-_-") (pintype "passive"))
      (node (ref "C87") (pin "1") (pinfunction "1_1") (pintype "passive"))
      (node (ref "C88") (pin "1") (pinfunction "1_1") (pintype "passive"))
      (node (ref "C89") (pin "-") (pinfunction "-_-") (pintype "passive"))
      (node (ref "C9") (pin "1") (pinfunction "1_1") (pintype "passive"))
      (node (ref "C90") (pin "-") (pinfunction "-_-") (pintype "passive"))
      (node (ref "C91") (pin "-") (pinfunction "-_-") (pintype "passive"))
      (node (ref "D1") (pin "A") (pinfunction "A_A") (pintype "passive"))
      (node (ref "D2") (pin "C") (pinfunction "C_C") (pintype "passive"))
      (node (ref "D3") (pin "A") (pinfunction "A_A") (pintype "passive"))
      (node (ref "IC6") (pin "1") (pinfunction "GND_1") (pintype "input"))
      (node (ref "IC7") (pin "10") (pinfunction "I1_10") (pintype "input"))
      (node (ref "IC7") (pin "12") (pinfunction "I0_12") (pintype "input"))
      (node (ref "IC7") (pin "13") (pinfunction "I1_13") (pintype "input"))
      (node (ref "IC7") (pin "4") (pinfunction "I0_4") (pintype "input"))
      (node (ref "IC7") (pin "5") (pinfunction "I1_5") (pintype "input"))
      (node (ref "IC7") (pin "7") (pinfunction "GND_7") (pintype "power_in"))
      (node (ref "IC7") (pin "9") (pinfunction "I0_9") (pintype "input"))
      (node (ref "INL") (pin "CONTACT") (pinfunction "SWITCH_CONTACT") (pintype "passive"))
      (node (ref "INL") (pin "GND") (pinfunction "GND_GND") (pintype "passive"))
      (node (ref "INR") (pin "CONTACT") (pinfunction "SWITCH_CONTACT") (pintype "passive"))
      (node (ref "INR") (pin "GND") (pinfunction "GND_GND") (pintype "passive"))
      (node (ref "OUTL") (pin "GND") (pinfunction "GND_GND") (pintype "passive"))
      (node (ref "OUTR") (pin "GND") (pinfunction "GND_GND") (pintype "passive"))
      (node (ref "R16") (pin "2") (pinfunction "2_2") (pintype "passive"))
      (node (ref "R17") (pin "2") (pinfunction "2_2") (pintype "passive"))
      (node (ref "R27") (pin "2") (pinfunction "2_2") (pintype "passive"))
      (node (ref "R28") (pin "2") (pinfunction "2_2") (pintype "passive"))
      (node (ref "R33") (pin "1") (pinfunction "1_1") (pintype "passive"))
      (node (ref "R36") (pin "2") (pinfunction "2_2") (pintype "passive"))
      (node (ref "R59") (pin "2") (pinfunction "2_2") (pintype "passive"))
      (node (ref "R6") (pin "1") (pinfunction "1_1") (pintype "passive"))
      (node (ref "SJ3") (pin "1") (pinfunction "1_1") (pintype "passive"))
      (node (ref "SV1") (pin "1") (pinfunction "1_1") (pintype "passive"))
      (node (ref "SV3") (pin "1") (pinfunction "1_1") (pintype "passive"))
      (node (ref "SV4") (pin "6") (pinfunction "6_6") (pintype "passive"))
      (node (ref "U$3") (pin "P$2") (pinfunction "GND_P$2") (pintype "power_in"))
      (node (ref "U$4") (pin "P$2") (pinfunction "GND_P$2") (pintype "power_in"))
      (node (ref "U1") (pin "1") (pinfunction "DGND_1") (pintype "bidirectional"))
      (node (ref "U1") (pin "11") (pinfunction "AGND_11") (pintype "bidirectional"))
      (node (ref "U1") (pin "20") (pinfunction "IDPM1_20") (pintype "bidirectional"))
      (node (ref "U1") (pin "21") (pinfunction "IDPM0_21") (pintype "bidirectional"))
      (node (ref "U1") (pin "23") (pinfunction "MUTE_23") (pintype "bidirectional"))
      (node (ref "U1") (pin "7") (pinfunction "INT8X_7") (pintype "bidirectional"))
      (node (ref "U1") (pin "9") (pinfunction "DEEMP_9") (pintype "bidirectional"))
      (node (ref "U2") (pin "15") (pinfunction "AGND_15") (pintype "bidirectional"))
      (node (ref "U2") (pin "20") (pinfunction "AGND_20") (pintype "bidirectional"))
      (node (ref "U2") (pin "21") (pinfunction "CASC_21") (pintype "bidirectional"))
      (node (ref "U2") (pin "22") (pinfunction "DGND_22") (pintype "bidirectional"))
      (node (ref "U2") (pin "7") (pinfunction "DGND_7") (pintype "bidirectional"))
      (node (ref "U2") (pin "8") (pinfunction "XCTRL_8") (pintype "bidirectional"))
      (node (ref "U5") (pin "4") (pinfunction "GND_4") (pintype "bidirectional"))
      (node (ref "U6") (pin "4") (pinfunction "GND_4") (pintype "bidirectional"))
      (node (ref "U7") (pin "12") (pinfunction "GND_12") (pintype "bidirectional"))
      (node (ref "U7") (pin "27") (pinfunction "GND0_27") (pintype "bidirectional"))
      (node (ref "U7") (pin "3") (pinfunction "GNDA_3") (pintype "bidirectional"))
      (node (ref "U7") (pin "32") (pinfunction "#WAKE_32") (pintype "bidirectional"))
      (node (ref "U7") (pin "34") (pinfunction "XOSC0_34") (pintype "bidirectional"))
      (node (ref "U7") (pin "35") (pinfunction "XGND_35") (pintype "bidirectional"))
      (node (ref "U7") (pin "39") (pinfunction "GND1_39") (pintype "bidirectional"))
      (node (ref "U7") (pin "55") (pinfunction "GND2_55") (pintype "bidirectional"))
      (node (ref "X1") (pin "5") (pinfunction "5_5") (pintype "input"))
      (node (ref "X3") (pin "2") (pinfunction "S_2") (pintype "passive"))
      (node (ref "X3") (pin "3") (pinfunction "S_3") (pintype "passive"))
      (node (ref "X3") (pin "5") (pinfunction "S_5") (pintype "passive"))
      (node (ref "X7") (pin "GND") (pinfunction "GND_GND") (pintype "bidirectional"))
    )
    (net (code "16") (name "Net-(C1-Pad+)") (class "Default")
      (node (ref "C1") (pin "+") (pinfunction "+_+") (pintype "passive"))
      (node (ref "C77") (pin "2") (pinfunction "2_2") (pintype "passive"))
      (node (ref "R40") (pin "2") (pinfunction "2_2") (pintype "passive"))
    )
    (net (code "17") (name "Net-(C1-Pad-)") (class "Default")
      (node (ref "C1") (pin "-") (pinfunction "-_-") (pintype "passive"))
      (node (ref "C77") (pin "1") (pinfunction "1_1") (pintype "passive"))
      (node (ref "JP1") (pin "1") (pinfunction "1_1") (pintype "passive"))
      (node (ref "R44") (pin "1") (pinfunction "1_1") (pintype "passive"))
    )
    (net (code "18") (name "Net-(C2-Pad+)") (class "Default")
      (node (ref "C2") (pin "+") (pinfunction "+_+") (pintype "passive"))
      (node (ref "C78") (pin "2") (pinfunction "2_2") (pintype "passive"))
      (node (ref "R49") (pin "1") (pinfunction "1_1") (pintype "passive"))
    )
    (net (code "19") (name "Net-(C2-Pad-)") (class "Default")
      (node (ref "C2") (pin "-") (pinfunction "-_-") (pintype "passive"))
      (node (ref "C78") (pin "1") (pinfunction "1_1") (pintype "passive"))
      (node (ref "JP2") (pin "1") (pinfunction "1_1") (pintype "passive"))
      (node (ref "R48") (pin "2") (pinfunction "2_2") (pintype "passive"))
    )
    (net (code "20") (name "Net-(C5-Pad+)") (class "Default")
      (node (ref "C5") (pin "+") (pinfunction "+_+") (pintype "passive"))
      (node (ref "R43") (pin "1") (pinfunction "1_1") (pintype "passive"))
      (node (ref "SJ2") (pin "2") (pinfunction "2_2") (pintype "passive"))
      (node (ref "X1") (pin "1") (pinfunction "1_1") (pintype "input"))
      (node (ref "X7") (pin "VBUS") (pinfunction "VBUS_VBUS") (pintype "bidirectional"))
    )
    (net (code "21") (name "Net-(C9-Pad2)") (class "Default")
      (node (ref "C9") (pin "2") (pinfunction "2_2") (pintype "passive"))
      (node (ref "JP1") (pin "2") (pinfunction "2_2") (pintype "passive"))
      (node (ref "R4") (pin "1") (pinfunction "1_1") (pintype "passive"))
      (node (ref "R44") (pin "2") (pinfunction "2_2") (pintype "passive"))
    )
    (net (code "22") (name "Net-(C10-Pad2)") (class "Default")
      (node (ref "C10") (pin "2") (pinfunction "2_2") (pintype "passive"))
      (node (ref "JP2") (pin "2") (pinfunction "2_2") (pintype "passive"))
      (node (ref "R48") (pin "1") (pinfunction "1_1") (pintype "passive"))
      (node (ref "R5") (pin "1") (pinfunction "1_1") (pintype "passive"))
    )
    (net (code "23") (name "Net-(C25-Pad1)") (class "Default")
      (node (ref "C25") (pin "1") (pinfunction "1_1") (pintype "passive"))
      (node (ref "R11") (pin "1") (pinfunction "1_1") (pintype "passive"))
      (node (ref "R12") (pin "2") (pinfunction "2_2") (pintype "passive"))
      (node (ref "R13") (pin "2") (pinfunction "2_2") (pintype "passive"))
    )
    (net (code "24") (name "Net-(C26-Pad2)") (class "Default")
      (node (ref "C26") (pin "2") (pinfunction "2_2") (pintype "passive"))
      (node (ref "R14") (pin "1") (pinfunction "1_1") (pintype "passive"))
      (node (ref "R15") (pin "2") (pinfunction "2_2") (pintype "passive"))
      (node (ref "R16") (pin "1") (pinfunction "1_1") (pintype "passive"))
    )
    (net (code "25") (name "Net-(C37-Pad1)") (class "Default")
      (node (ref "C37") (pin "1") (pinfunction "1_1") (pintype "passive"))
      (node (ref "R22") (pin "1") (pinfunction "1_1") (pintype "passive"))
      (node (ref "R23") (pin "2") (pinfunction "2_2") (pintype "passive"))
      (node (ref "R24") (pin "2") (pinfunction "2_2") (pintype "passive"))
    )
    (net (code "26") (name "Net-(C38-Pad2)") (class "Default")
      (node (ref "C38") (pin "2") (pinfunction "2_2") (pintype "passive"))
      (node (ref "R25") (pin "1") (pinfunction "1_1") (pintype "passive"))
      (node (ref "R26") (pin "2") (pinfunction "2_2") (pintype "passive"))
      (node (ref "R27") (pin "1") (pinfunction "1_1") (pintype "passive"))
    )
    (net (code "27") (name "Net-(IC1A-+IN)") (class "Default")
      (node (ref "IC1") (pin "3") (pinfunction "+IN_3") (pintype "input"))
      (node (ref "IC1") (pin "5") (pinfunction "+IN_5") (pintype "input"))
      (node (ref "R8") (pin "1") (pinfunction "1_1") (pintype "passive"))
    )
    (net (code "28") (name "Net-(IC1A--IN)") (class "Default")
      (node (ref "C22") (pin "2") (pinfunction "2_2") (pintype "passive"))
      (node (ref "C24") (pin "1") (pinfunction "1_1") (pintype "passive"))
      (node (ref "IC1") (pin "2") (pinfunction "-IN_2") (pintype "input"))
      (node (ref "R9") (pin "2") (pinfunction "2_2") (pintype "passive"))
      (node (ref "U1") (pin "16") (pinfunction "ROUT-_16") (pintype "bidirectional"))
    )
    (net (code "29") (name "Net-(IC1A-OUT)") (class "Default")
      (node (ref "C24") (pin "2") (pinfunction "2_2") (pintype "passive"))
      (node (ref "IC1") (pin "1") (pinfunction "OUT_1") (pintype "output"))
      (node (ref "R14") (pin "2") (pinfunction "2_2") (pintype "passive"))
      (node (ref "R9") (pin "1") (pinfunction "1_1") (pintype "passive"))
    )
    (net (code "30") (name "Net-(IC1B--IN)") (class "Default")
      (node (ref "C22") (pin "1") (pinfunction "1_1") (pintype "passive"))
      (node (ref "C23") (pin "1") (pinfunction "1_1") (pintype "passive"))
      (node (ref "IC1") (pin "6") (pinfunction "-IN_6") (pintype "input"))
      (node (ref "R7") (pin "2") (pinfunction "2_2") (pintype "passive"))
      (node (ref "U1") (pin "17") (pinfunction "ROUT+_17") (pintype "bidirectional"))
    )
    (net (code "31") (name "Net-(IC1B-OUT)") (class "Default")
      (node (ref "C23") (pin "2") (pinfunction "2_2") (pintype "passive"))
      (node (ref "IC1") (pin "7") (pinfunction "OUT_7") (pintype "output"))
      (node (ref "R11") (pin "2") (pinfunction "2_2") (pintype "passive"))
      (node (ref "R7") (pin "1") (pinfunction "1_1") (pintype "passive"))
    )
    (net (code "32") (name "Net-(IC2A-+IN)") (class "Default")
      (node (ref "C40") (pin "1") (pinfunction "1_1") (pintype "passive"))
      (node (ref "IC2") (pin "3") (pinfunction "+IN_3") (pintype "input"))
      (node (ref "R26") (pin "1") (pinfunction "1_1") (pintype "passive"))
    )
    (net (code "33") (name "Net-(IC2A--IN)") (class "Default")
      (node (ref "C39") (pin "2") (pinfunction "2_2") (pintype "passive"))
      (node (ref "IC2") (pin "2") (pinfunction "-IN_2") (pintype "input"))
      (node (ref "R23") (pin "1") (pinfunction "1_1") (pintype "passive"))
    )
    (net (code "34") (name "Net-(IC2A-OUT)") (class "Default")
      (node (ref "C39") (pin "1") (pinfunction "1_1") (pintype "passive"))
      (node (ref "IC2") (pin "1") (pinfunction "OUT_1") (pintype "output"))
      (node (ref "R21") (pin "2") (pinfunction "2_2") (pintype "passive"))
      (node (ref "R24") (pin "1") (pinfunction "1_1") (pintype "passive"))
    )
    (net (code "35") (name "Net-(IC2B-+IN)") (class "Default")
      (node (ref "C28") (pin "1") (pinfunction "1_1") (pintype "passive"))
      (node (ref "IC2") (pin "5") (pinfunction "+IN_5") (pintype "input"))
      (node (ref "R15") (pin "1") (pinfunction "1_1") (pintype "passive"))
    )
    (net (code "36") (name "Net-(IC2B--IN)") (class "Default")
      (node (ref "C27") (pin "2") (pinfunction "2_2") (pintype "passive"))
      (node (ref "IC2") (pin "6") (pinfunction "-IN_6") (pintype "input"))
      (node (ref "R12") (pin "1") (pinfunction "1_1") (pintype "passive"))
    )
    (net (code "37") (name "Net-(IC2B-OUT)") (class "Default")
      (node (ref "C27") (pin "1") (pinfunction "1_1") (pintype "passive"))
      (node (ref "IC2") (pin "7") (pinfunction "OUT_7") (pintype "output"))
      (node (ref "R10") (pin "2") (pinfunction "2_2") (pintype "passive"))
      (node (ref "R13") (pin "1") (pinfunction "1_1") (pintype "passive"))
    )
    (net (code "38") (name "Net-(IC3A-+IN)") (class "Default")
      (node (ref "C12") (pin "1") (pinfunction "1_1") (pintype "passive"))
      (node (ref "C21") (pin "1") (pinfunction "1_1") (pintype "passive"))
      (node (ref "C3") (pin "+") (pinfunction "+_+") (pintype "passive"))
      (node (ref "C79") (pin "1") (pinfunction "1_1") (pintype "passive"))
      (node (ref "IC3") (pin "3") (pinfunction "+IN_3") (pintype "input"))
      (node (ref "IC3") (pin "5") (pinfunction "+IN_5") (pintype "input"))
      (node (ref "IC8") (pin "3") (pinfunction "+IN_3") (pintype "input"))
      (node (ref "IC8") (pin "5") (pinfunction "+IN_5") (pintype "input"))
      (node (ref "R53") (pin "2") (pinfunction "2_2") (pintype "passive"))
      (node (ref "R54") (pin "2") (pinfunction "2_2") (pintype "passive"))
      (node (ref "U2") (pin "10") (pinfunction "VINLN_10") (pintype "bidirectional"))
      (node (ref "U2") (pin "14") (pinfunction "VREF_14") (pintype "bidirectional"))
      (node (ref "U2") (pin "19") (pinfunction "VINRN_19") (pintype "bidirectional"))
    )
    (net (code "39") (name "Net-(IC3A--IN)") (class "Default")
      (node (ref "C18") (pin "2") (pinfunction "2_2") (pintype "passive"))
      (node (ref "IC3") (pin "2") (pinfunction "-IN_2") (pintype "input"))
      (node (ref "R40") (pin "1") (pinfunction "1_1") (pintype "passive"))
      (node (ref "R47") (pin "2") (pinfunction "2_2") (pintype "passive"))
    )
    (net (code "40") (name "Net-(IC3A-OUT)") (class "Default")
      (node (ref "C18") (pin "1") (pinfunction "1_1") (pintype "passive"))
      (node (ref "IC3") (pin "1") (pinfunction "OUT_1") (pintype "output"))
      (node (ref "R41") (pin "2") (pinfunction "2_2") (pintype "passive"))
      (node (ref "R47") (pin "1") (pinfunction "1_1") (pintype "passive"))
      (node (ref "R55") (pin "2") (pinfunction "2_2") (pintype "passive"))
    )
    (net (code "41") (name "Net-(IC3B--IN)") (class "Default")
      (node (ref "IC3") (pin "6") (pinfunction "-IN_6") (pintype "input"))
      (node (ref "R41") (pin "1") (pinfunction "1_1") (pintype "passive"))
      (node (ref "R46") (pin "2") (pinfunction "2_2") (pintype "passive"))
      (node (ref "R54") (pin "1") (pinfunction "1_1") (pintype "passive"))
    )
    (net (code "42") (name "Net-(IC3B-OUT)") (class "Default")
      (node (ref "IC3") (pin "7") (pinfunction "OUT_7") (pintype "output"))
      (node (ref "R46") (pin "1") (pinfunction "1_1") (pintype "passive"))
      (node (ref "R56") (pin "2") (pinfunction "2_2") (pintype "passive"))
    )
    (net (code "43") (name "Net-(IC6-OUT)") (class "Default")
      (node (ref "C57") (pin "+") (pinfunction "+_+") (pintype "passive"))
      (node (ref "C65") (pin "+") (pinfunction "+_+") (pintype "passive"))
      (node (ref "C67") (pin "2") (pinfunction "2_2") (pintype "passive"))
      (node (ref "C68") (pin "2") (pinfunction "2_2") (pintype "passive"))
      (node (ref "C69") (pin "2") (pinfunction "2_2") (pintype "passive"))
      (node (ref "C70") (pin "2") (pinfunction "2_2") (pintype "passive"))
      (node (ref "C74") (pin "2") (pinfunction "2_2") (pintype "passive"))
      (node (ref "IC6") (pin "2") (pinfunction "OUT_2") (pintype "passive"))
      (node (ref "IC7") (pin "14") (pinfunction "VCC_14") (pintype "power_in"))
      (node (ref "L2") (pin "2") (pinfunction "2_2") (pintype "passive"))
      (node (ref "R2") (pin "2") (pinfunction "2_2") (pintype "passive"))
      (node (ref "R37") (pin "2") (pinfunction "2_2") (pintype "passive"))
      (node (ref "R45") (pin "2") (pinfunction "2_2") (pintype "passive"))
      (node (ref "U7") (pin "11") (pinfunction "VDD_11") (pintype "bidirectional"))
      (node (ref "U7") (pin "2") (pinfunction "VDDA_2") (pintype "bidirectional"))
      (node (ref "U7") (pin "26") (pinfunction "VDD1_26") (pintype "bidirectional"))
      (node (ref "U7") (pin "37") (pinfunction "VBAT_37") (pintype "bidirectional"))
      (node (ref "U7") (pin "42") (pinfunction "VDD2_42") (pintype "bidirectional"))
      (node (ref "U7") (pin "54") (pinfunction "VDD3_54") (pintype "bidirectional"))
    )
    (net (code "44") (name "Net-(IC7A-I1)") (class "Default")
      (node (ref "IC7") (pin "2") (pinfunction "I1_2") (pintype "input"))
      (node (ref "U7") (pin "10") (pinfunction "PD7_10") (pintype "bidirectional"))
    )
    (net (code "45") (name "Net-(IC7A-O)") (class "Default")
      (node (ref "IC7") (pin "3") (pinfunction "O_3") (pintype "output"))
      (node (ref "U7") (pin "57") (pinfunction "PB5_57") (pintype "bidirectional"))
    )
    (net (code "46") (name "Net-(IC8A--IN)") (class "Default")
      (node (ref "IC8") (pin "2") (pinfunction "-IN_2") (pintype "input"))
      (node (ref "R51") (pin "1") (pinfunction "1_1") (pintype "passive"))
      (node (ref "R52") (pin "2") (pinfunction "2_2") (pintype "passive"))
      (node (ref "R53") (pin "1") (pinfunction "1_1") (pintype "passive"))
    )
    (net (code "47") (name "Net-(IC8A-OUT)") (class "Default")
      (node (ref "IC8") (pin "1") (pinfunction "OUT_1") (pintype "output"))
      (node (ref "R52") (pin "1") (pinfunction "1_1") (pintype "passive"))
      (node (ref "R57") (pin "2") (pinfunction "2_2") (pintype "passive"))
    )
    (net (code "48") (name "Net-(IC8B--IN)") (class "Default")
      (node (ref "C45") (pin "2") (pinfunction "2_2") (pintype "passive"))
      (node (ref "IC8") (pin "6") (pinfunction "-IN_6") (pintype "input"))
      (node (ref "R49") (pin "2") (pinfunction "2_2") (pintype "passive"))
      (node (ref "R50") (pin "2") (pinfunction "2_2") (pintype "passive"))
    )
    (net (code "49") (name "Net-(IC8B-OUT)") (class "Default")
      (node (ref "C45") (pin "1") (pinfunction "1_1") (pintype "passive"))
      (node (ref "IC8") (pin "7") (pinfunction "OUT_7") (pintype "output"))
      (node (ref "R50") (pin "1") (pinfunction "1_1") (pintype "passive"))
      (node (ref "R51") (pin "2") (pinfunction "2_2") (pintype "passive"))
      (node (ref "R58") (pin "2") (pinfunction "2_2") (pintype "passive"))
    )
    (net (code "50") (name "Net-(IC9A-+IN)") (class "Default")
      (node (ref "IC9") (pin "3") (pinfunction "+IN_3") (pintype "input"))
      (node (ref "IC9") (pin "5") (pinfunction "+IN_5") (pintype "input"))
      (node (ref "R19") (pin "1") (pinfunction "1_1") (pintype "passive"))
    )
    (net (code "51") (name "Net-(IC9A--IN)") (class "Default")
      (node (ref "C34") (pin "1") (pinfunction "1_1") (pintype "passive"))
      (node (ref "C35") (pin "1") (pinfunction "1_1") (pintype "passive"))
      (node (ref "IC9") (pin "2") (pinfunction "-IN_2") (pintype "input"))
      (node (ref "R18") (pin "2") (pinfunction "2_2") (pintype "passive"))
      (node (ref "U1") (pin "12") (pinfunction "LOUT+_12") (pintype "bidirectional"))
    )
    (net (code "52") (name "Net-(IC9A-OUT)") (class "Default")
      (node (ref "C35") (pin "2") (pinfunction "2_2") (pintype "passive"))
      (node (ref "IC9") (pin "1") (pinfunction "OUT_1") (pintype "output"))
      (node (ref "R18") (pin "1") (pinfunction "1_1") (pintype "passive"))
      (node (ref "R22") (pin "2") (pinfunction "2_2") (pintype "passive"))
    )
    (net (code "53") (name "Net-(IC9B--IN)") (class "Default")
      (node (ref "C34") (pin "2") (pinfunction "2_2") (pintype "passive"))
      (node (ref "C36") (pin "1") (pinfunction "1_1") (pintype "passive"))
      (node (ref "IC9") (pin "6") (pinfunction "-IN_6") (pintype "input"))
      (node (ref "R20") (pin "2") (pinfunction "2_2") (pintype "passive"))
      (node (ref "U1") (pin "13") (pinfunction "LOUT-_13") (pintype "bidirectional"))
    )
    (net (code "54") (name "Net-(IC9B-OUT)") (class "Default")
      (node (ref "C36") (pin "2") (pinfunction "2_2") (pintype "passive"))
      (node (ref "IC9") (pin "7") (pinfunction "OUT_7") (pintype "output"))
      (node (ref "R20") (pin "1") (pinfunction "1_1") (pintype "passive"))
      (node (ref "R25") (pin "2") (pinfunction "2_2") (pintype "passive"))
    )
    (net (code "55") (name "Net-(INL-HOT)") (class "Default")
      (node (ref "INL") (pin "TIP") (pinfunction "HOT_TIP") (pintype "passive"))
      (node (ref "R4") (pin "2") (pinfunction "2_2") (pintype "passive"))
    )
    (net (code "56") (name "Net-(INR-HOT)") (class "Default")
      (node (ref "INR") (pin "TIP") (pinfunction "HOT_TIP") (pintype "passive"))
      (node (ref "R5") (pin "2") (pinfunction "2_2") (pintype "passive"))
    )
    (net (code "57") (name "Net-(LED1-C)") (class "Default")
      (node (ref "LED1") (pin "K") (pinfunction "C_K") (pintype "passive"))
      (node (ref "R38") (pin "2") (pinfunction "2_2") (pintype "passive"))
    )
    (net (code "58") (name "Net-(LED2-C)") (class "Default")
      (node (ref "LED2") (pin "K") (pinfunction "C_K") (pintype "passive"))
      (node (ref "R33") (pin "2") (pinfunction "2_2") (pintype "passive"))
    )
    (net (code "59") (name "Net-(OUTL-HOT)") (class "Default")
      (node (ref "C41") (pin "1") (pinfunction "1_1") (pintype "passive"))
      (node (ref "OUTL") (pin "CONTACT") (pinfunction "SWITCH_CONTACT") (pintype "passive"))
      (node (ref "OUTL") (pin "TIP") (pinfunction "HOT_TIP") (pintype "passive"))
      (node (ref "R21") (pin "1") (pinfunction "1_1") (pintype "passive"))
      (node (ref "R28") (pin "1") (pinfunction "1_1") (pintype "passive"))
    )
    (net (code "60") (name "Net-(OUTR-HOT)") (class "Default")
      (node (ref "C29") (pin "1") (pinfunction "1_1") (pintype "passive"))
      (node (ref "OUTR") (pin "CONTACT") (pinfunction "SWITCH_CONTACT") (pintype "passive"))
      (node (ref "OUTR") (pin "TIP") (pinfunction "HOT_TIP") (pintype "passive"))
      (node (ref "R10") (pin "1") (pinfunction "1_1") (pintype "passive"))
      (node (ref "R17") (pin "1") (pinfunction "1_1") (pintype "passive"))
    )
    (net (code "61") (name "Net-(R31-Pad1)") (class "Default")
      (node (ref "R31") (pin "1") (pinfunction "1_1") (pintype "passive"))
      (node (ref "X1") (pin "4") (pinfunction "4_4") (pintype "input"))
    )
    (net (code "62") (name "Net-(R39-Pad1)") (class "Default")
      (node (ref "R39") (pin "1") (pinfunction "1_1") (pintype "passive"))
      (node (ref "SV4") (pin "4") (pinfunction "4_4") (pintype "passive"))
    )
    (net (code "63") (name "Net-(R42-Pad1)") (class "Default")
      (node (ref "R42") (pin "1") (pinfunction "1_1") (pintype "passive"))
      (node (ref "SV4") (pin "3") (pinfunction "3_3") (pintype "passive"))
    )
    (net (code "64") (name "Net-(U$3-FO)") (class "Default")
      (node (ref "R35") (pin "1") (pinfunction "1_1") (pintype "passive"))
      (node (ref "U$3") (pin "P$3") (pinfunction "FO_P$3") (pintype "output"))
    )
    (net (code "65") (name "Net-(U$3-OE)") (class "Default")
      (node (ref "U$3") (pin "P$1") (pinfunction "OE_P$1") (pintype "input"))
      (node (ref "U7") (pin "13") (pinfunction "PC7_13") (pintype "bidirectional"))
    )
    (net (code "66") (name "Net-(U$3-VCC)") (class "Default")
      (node (ref "C52") (pin "2") (pinfunction "2_2") (pintype "passive"))
      (node (ref "C53") (pin "2") (pinfunction "2_2") (pintype "passive"))
      (node (ref "C54") (pin "+") (pinfunction "+_+") (pintype "passive"))
      (node (ref "U$3") (pin "P$4") (pinfunction "VCC_P$4") (pintype "power_in"))
      (node (ref "U$4") (pin "P$4") (pinfunction "VCC_P$4") (pintype "power_in"))
      (node (ref "U6") (pin "2") (pinfunction "VOUT_2") (pintype "bidirectional"))
    )
    (net (code "67") (name "Net-(U$4-FO)") (class "Default")
      (node (ref "R34") (pin "1") (pinfunction "1_1") (pintype "passive"))
      (node (ref "U$4") (pin "P$3") (pinfunction "FO_P$3") (pintype "output"))
    )
    (net (code "68") (name "Net-(U$4-OE)") (class "Default")
      (node (ref "U$4") (pin "P$1") (pinfunction "OE_P$1") (pintype "input"))
      (node (ref "U7") (pin "14") (pinfunction "PC6_14") (pintype "bidirectional"))
    )
    (net (code "69") (name "Net-(U1-DVDD)") (class "Default")
      (node (ref "C20") (pin "1") (pinfunction "1_1") (pintype "passive"))
      (node (ref "C81") (pin "+") (pinfunction "+_+") (pintype "passive"))
      (node (ref "L3") (pin "2") (pinfunction "2_2") (pintype "passive"))
      (node (ref "U1") (pin "28") (pinfunction "DVDD_28") (pintype "bidirectional"))
    )
    (net (code "70") (name "Net-(U1-FCR)") (class "Default")
      (node (ref "C48") (pin "1") (pinfunction "1_1") (pintype "passive"))
      (node (ref "C49") (pin "-") (pinfunction "-_-") (pintype "passive"))
      (node (ref "U1") (pin "15") (pinfunction "FCR_15") (pintype "bidirectional"))
    )
    (net (code "71") (name "Net-(U1-FILTB)") (class "Default")
      (node (ref "C48") (pin "2") (pinfunction "2_2") (pintype "passive"))
      (node (ref "C49") (pin "+") (pinfunction "+_+") (pintype "passive"))
      (node (ref "U1") (pin "19") (pinfunction "FILTB_19") (pintype "bidirectional"))
    )
    (net (code "72") (name "Net-(U1-FILTR)") (class "Default")
      (node (ref "C46") (pin "+") (pinfunction "+_+") (pintype "passive"))
      (node (ref "C47") (pin "2") (pinfunction "2_2") (pintype "passive"))
      (node (ref "R19") (pin "2") (pinfunction "2_2") (pintype "passive"))
      (node (ref "R8") (pin "2") (pinfunction "2_2") (pintype "passive"))
      (node (ref "U1") (pin "14") (pinfunction "FILTR_14") (pintype "bidirectional"))
    )
    (net (code "73") (name "Net-(U1-IREF)") (class "Default")
      (node (ref "R6") (pin "2") (pinfunction "2_2") (pintype "passive"))
      (node (ref "U1") (pin "10") (pinfunction "IREF_10") (pintype "bidirectional"))
    )
    (net (code "74") (name "Net-(U1-MCLK)") (class "Default")
      (node (ref "R34") (pin "2") (pinfunction "2_2") (pintype "passive"))
      (node (ref "R35") (pin "2") (pinfunction "2_2") (pintype "passive"))
      (node (ref "R36") (pin "1") (pinfunction "1_1") (pintype "passive"))
      (node (ref "U1") (pin "2") (pinfunction "MCLK_2") (pintype "bidirectional"))
      (node (ref "U2") (pin "1") (pinfunction "MCLK_1") (pintype "bidirectional"))
    )
    (net (code "75") (name "Net-(U1-RST)") (class "Default")
      (node (ref "R59") (pin "1") (pinfunction "1_1") (pintype "passive"))
      (node (ref "U1") (pin "24") (pinfunction "RST_24") (pintype "bidirectional"))
      (node (ref "U2") (pin "24") (pinfunction "RESET_24") (pintype "bidirectional"))
      (node (ref "U7") (pin "31") (pinfunction "PF3_31") (pintype "bidirectional"))
    )
    (net (code "76") (name "Net-(U1-SDATA)") (class "Default")
      (node (ref "R30") (pin "1") (pinfunction "1_1") (pintype "passive"))
      (node (ref "U1") (pin "27") (pinfunction "SDATA_27") (pintype "bidirectional"))
    )
    (net (code "77") (name "Net-(U2-BCLK)") (class "Default")
      (node (ref "R3") (pin "2") (pinfunction "2_2") (pintype "passive"))
      (node (ref "U2") (pin "27") (pinfunction "BCLK_27") (pintype "bidirectional"))
    )
    (net (code "78") (name "Net-(U2-CAPLN)") (class "Default")
      (node (ref "C6") (pin "2") (pinfunction "2_2") (pintype "passive"))
      (node (ref "C8") (pin "1") (pinfunction "1_1") (pintype "passive"))
      (node (ref "R56") (pin "1") (pinfunction "1_1") (pintype "passive"))
      (node (ref "U2") (pin "12") (pinfunction "CAPLN_12") (pintype "bidirectional"))
    )
    (net (code "79") (name "Net-(U2-CAPLP)") (class "Default")
      (node (ref "C6") (pin "1") (pinfunction "1_1") (pintype "passive"))
      (node (ref "C7") (pin "1") (pinfunction "1_1") (pintype "passive"))
      (node (ref "R55") (pin "1") (pinfunction "1_1") (pintype "passive"))
      (node (ref "U2") (pin "13") (pinfunction "CAPLP_13") (pintype "bidirectional"))
    )
    (net (code "80") (name "Net-(U2-CAPRN)") (class "Default")
      (node (ref "C11") (pin "1") (pinfunction "1_1") (pintype "passive"))
      (node (ref "C15") (pin "2") (pinfunction "2_2") (pintype "passive"))
      (node (ref "R57") (pin "1") (pinfunction "1_1") (pintype "passive"))
      (node (ref "U2") (pin "17") (pinfunction "CAPRN_17") (pintype "bidirectional"))
    )
    (net (code "81") (name "Net-(U2-CAPRP)") (class "Default")
      (node (ref "C11") (pin "2") (pinfunction "2_2") (pintype "passive"))
      (node (ref "C14") (pin "2") (pinfunction "2_2") (pintype "passive"))
      (node (ref "R58") (pin "1") (pinfunction "1_1") (pintype "passive"))
      (node (ref "U2") (pin "16") (pinfunction "CAPRP_16") (pintype "bidirectional"))
    )
    (net (code "82") (name "Net-(U2-COUT)") (class "Default")
      (node (ref "R29") (pin "2") (pinfunction "2_2") (pintype "passive"))
      (node (ref "U2") (pin "3") (pinfunction "COUT_3") (pintype "bidirectional"))
    )
    (net (code "83") (name "Net-(U2-DOUT)") (class "Default")
      (node (ref "R1") (pin "2") (pinfunction "2_2") (pintype "passive"))
      (node (ref "U2") (pin "26") (pinfunction "DOUT_26") (pintype "bidirectional"))
    )
    (net (code "84") (name "Net-(U2-DVDD)") (class "Default")
      (node (ref "C16") (pin "1") (pinfunction "1_1") (pintype "passive"))
      (node (ref "C83") (pin "+") (pinfunction "+_+") (pintype "passive"))
      (node (ref "L1") (pin "2") (pinfunction "2_2") (pintype "passive"))
      (node (ref "U2") (pin "6") (pinfunction "DVDD_6") (pintype "bidirectional"))
    )
    (net (code "85") (name "Net-(U2-LRCLK)") (class "Default")
      (node (ref "R32") (pin "2") (pinfunction "2_2") (pintype "passive"))
      (node (ref "U2") (pin "28") (pinfunction "LRCLK_28") (pintype "bidirectional"))
    )
    (net (code "86") (name "Net-(U2-ODVDD)") (class "Default")
      (node (ref "C56") (pin "2") (pinfunction "2_2") (pintype "passive"))
      (node (ref "C84") (pin "+") (pinfunction "+_+") (pintype "passive"))
      (node (ref "L2") (pin "1") (pinfunction "1_1") (pintype "passive"))
      (node (ref "U2") (pin "23") (pinfunction "ODVDD_23") (pintype "bidirectional"))
    )
    (net (code "87") (name "Net-(U5-BYP)") (class "Default")
      (node (ref "C44") (pin "+") (pinfunction "+_+") (pintype "passive"))
      (node (ref "C88") (pin "2") (pinfunction "2_2") (pintype "passive"))
      (node (ref "U5") (pin "3") (pinfunction "BYP_3") (pintype "bidirectional"))
    )
    (net (code "88") (name "Net-(U5-REF)") (class "Default")
      (node (ref "C55") (pin "+") (pinfunction "+_+") (pintype "passive"))
      (node (ref "U5") (pin "5") (pinfunction "REF_SENSE_5") (pintype "bidirectional"))
      (node (ref "U5") (pin "6") (pinfunction "REF_6") (pintype "bidirectional"))
    )
    (net (code "89") (name "Net-(U5-VREG)") (class "Default")
      (node (ref "C91") (pin "+") (pinfunction "+_+") (pintype "passive"))
      (node (ref "U5") (pin "1") (pinfunction "VREG_1") (pintype "bidirectional"))
    )
    (net (code "90") (name "Net-(U6-BYP)") (class "Default")
      (node (ref "C60") (pin "+") (pinfunction "+_+") (pintype "passive"))
      (node (ref "C87") (pin "2") (pinfunction "2_2") (pintype "passive"))
      (node (ref "U6") (pin "3") (pinfunction "BYP_3") (pintype "bidirectional"))
    )
    (net (code "91") (name "Net-(U6-REF)") (class "Default")
      (node (ref "C61") (pin "+") (pinfunction "+_+") (pintype "passive"))
      (node (ref "U6") (pin "5") (pinfunction "REF_SENSE_5") (pintype "bidirectional"))
      (node (ref "U6") (pin "6") (pinfunction "REF_6") (pintype "bidirectional"))
    )
    (net (code "92") (name "Net-(U6-VREG)") (class "Default")
      (node (ref "C62") (pin "+") (pinfunction "+_+") (pintype "passive"))
      (node (ref "U6") (pin "1") (pinfunction "VREG_1") (pintype "bidirectional"))
    )
    (net (code "93") (name "Net-(U7A-#RESET)") (class "Default")
      (node (ref "C59") (pin "2") (pinfunction "2_2") (pintype "passive"))
      (node (ref "R37") (pin "1") (pinfunction "1_1") (pintype "passive"))
      (node (ref "SV3") (pin "6") (pinfunction "6_6") (pintype "passive"))
      (node (ref "U7") (pin "38") (pinfunction "#RESET_38") (pintype "bidirectional"))
    )
    (net (code "94") (name "Net-(U7A-OSC0)") (class "Default")
      (node (ref "C73") (pin "1") (pinfunction "1_1") (pintype "passive"))
      (node (ref "Q1") (pin "2") (pinfunction "2_2") (pintype "passive"))
      (node (ref "U7") (pin "40") (pinfunction "OSC0_40") (pintype "bidirectional"))
    )
    (net (code "95") (name "Net-(U7A-OSC1)") (class "Default")
      (node (ref "C72") (pin "1") (pinfunction "1_1") (pintype "passive"))
      (node (ref "Q1") (pin "1") (pinfunction "1_1") (pintype "passive"))
      (node (ref "U7") (pin "41") (pinfunction "OSC1_41") (pintype "bidirectional"))
    )
    (net (code "96") (name "Net-(U7A-VCCD)") (class "Default")
      (node (ref "C71") (pin "2") (pinfunction "2_2") (pintype "passive"))
      (node (ref "C75") (pin "+") (pinfunction "+_+") (pintype "passive"))
      (node (ref "U7") (pin "25") (pinfunction "VCCD_25") (pintype "bidirectional"))
      (node (ref "U7") (pin "56") (pinfunction "VCCD1_56") (pintype "bidirectional"))
    )
    (net (code "97") (name "Net-(U7B-PA0)") (class "Default")
      (node (ref "SV1") (pin "2") (pinfunction "2_2") (pintype "passive"))
      (node (ref "U7") (pin "17") (pinfunction "PA0_17") (pintype "bidirectional"))
    )
    (net (code "98") (name "Net-(U7B-PA1)") (class "Default")
      (node (ref "SV1") (pin "3") (pinfunction "3_3") (pintype "passive"))
      (node (ref "U7") (pin "18") (pinfunction "PA1_18") (pintype "bidirectional"))
    )
    (net (code "99") (name "Net-(U7B-PB2)") (class "Default")
      (node (ref "LED2") (pin "A") (pinfunction "A_A") (pintype "passive"))
      (node (ref "U7") (pin "47") (pinfunction "PB2_47") (pintype "bidirectional"))
    )
    (net (code "100") (name "Net-(U7B-PB3)") (class "Default")
      (node (ref "R38") (pin "1") (pinfunction "1_1") (pintype "passive"))
      (node (ref "U7") (pin "48") (pinfunction "PB3_48") (pintype "bidirectional"))
    )
    (net (code "101") (name "Net-(U7B-PC0)") (class "Default")
      (node (ref "SV3") (pin "2") (pinfunction "2_2") (pintype "passive"))
      (node (ref "U7") (pin "52") (pinfunction "PC0_52") (pintype "bidirectional"))
    )
    (net (code "102") (name "Net-(U7B-PC1)") (class "Default")
      (node (ref "SV3") (pin "3") (pinfunction "3_3") (pintype "passive"))
      (node (ref "U7") (pin "51") (pinfunction "PC1_51") (pintype "bidirectional"))
    )
    (net (code "103") (name "Net-(U7B-PC2)") (class "Default")
      (node (ref "SV3") (pin "5") (pinfunction "5_5") (pintype "passive"))
      (node (ref "U7") (pin "50") (pinfunction "PC2_50") (pintype "bidirectional"))
    )
    (net (code "104") (name "Net-(U7B-PC3)") (class "Default")
      (node (ref "SV3") (pin "4") (pinfunction "4_4") (pintype "passive"))
      (node (ref "U7") (pin "49") (pinfunction "PC3_49") (pintype "bidirectional"))
    )
    (net (code "105") (name "Net-(U7B-PD0)") (class "Default")
      (node (ref "R42") (pin "2") (pinfunction "2_2") (pintype "passive"))
      (node (ref "U7") (pin "61") (pinfunction "PD0_61") (pintype "bidirectional"))
    )
    (net (code "106") (name "Net-(U7B-PD1)") (class "Default")
      (node (ref "SV4") (pin "5") (pinfunction "5_5") (pintype "passive"))
      (node (ref "U7") (pin "62") (pinfunction "PD1_62") (pintype "bidirectional"))
    )
    (net (code "107") (name "Net-(U7B-PD2)") (class "Default")
      (node (ref "SV4") (pin "1") (pinfunction "1_1") (pintype "passive"))
      (node (ref "U7") (pin "63") (pinfunction "PD2_63") (pintype "bidirectional"))
    )
    (net (code "108") (name "Net-(U7B-PD3)") (class "Default")
      (node (ref "R39") (pin "2") (pinfunction "2_2") (pintype "passive"))
      (node (ref "U7") (pin "64") (pinfunction "PD3_64") (pintype "bidirectional"))
    )
    (net (code "109") (name "Net-(U7B-PD4)") (class "Default")
      (node (ref "U7") (pin "43") (pinfunction "PD4_43") (pintype "bidirectional"))
      (node (ref "X1") (pin "2") (pinfunction "2_2") (pintype "input"))
      (node (ref "X7") (pin "D-") (pinfunction "D-_D-") (pintype "bidirectional"))
    )
    (net (code "110") (name "Net-(U7B-PD5)") (class "Default")
      (node (ref "U7") (pin "44") (pinfunction "PD5_44") (pintype "bidirectional"))
      (node (ref "X1") (pin "3") (pinfunction "3_3") (pintype "input"))
      (node (ref "X7") (pin "D+") (pinfunction "D+_D+") (pintype "bidirectional"))
    )
    (net (code "111") (name "Net-(U7B-PD6)") (class "Default")
      (node (ref "LED1") (pin "A") (pinfunction "A_A") (pintype "passive"))
      (node (ref "U7") (pin "53") (pinfunction "PD6_53") (pintype "bidirectional"))
    )
    (net (code "112") (name "Net-(U7B-PE4)") (class "Default")
      (node (ref "SV4") (pin "7") (pinfunction "7_7") (pintype "passive"))
      (node (ref "U7") (pin "59") (pinfunction "PE4_59") (pintype "bidirectional"))
    )
    (net (code "113") (name "Net-(U7B-PE5)") (class "Default")
      (node (ref "SV4") (pin "8") (pinfunction "8_8") (pintype "passive"))
      (node (ref "U7") (pin "60") (pinfunction "PE5_60") (pintype "bidirectional"))
    )
    (net (code "114") (name "Net-(X1-GND4)") (class "Default")
      (node (ref "SJ3") (pin "2") (pinfunction "2_2") (pintype "passive"))
      (node (ref "X1") (pin "M4") (pinfunction "GND4_M4") (pintype "bidirectional"))
    )
    (net (code "115") (name "Net-(X3A-S)") (class "Default")
      (node (ref "SJ1") (pin "2") (pinfunction "2_2") (pintype "passive"))
      (node (ref "X3") (pin "1") (pinfunction "S_1") (pintype "passive"))
    )
    (net (code "116") (name "VCC") (class "Default")
      (node (ref "C13") (pin "2") (pinfunction "2_2") (pintype "passive"))
      (node (ref "C19") (pin "2") (pinfunction "2_2") (pintype "passive"))
      (node (ref "C58") (pin "+") (pinfunction "+_+") (pintype "passive"))
      (node (ref "C80") (pin "+") (pinfunction "+_+") (pintype "passive"))
      (node (ref "C82") (pin "+") (pinfunction "+_+") (pintype "passive"))
      (node (ref "C90") (pin "+") (pinfunction "+_+") (pintype "passive"))
      (node (ref "U1") (pin "18") (pinfunction "AVDD_18") (pintype "bidirectional"))
      (node (ref "U2") (pin "9") (pinfunction "AVDD_9") (pintype "bidirectional"))
      (node (ref "U5") (pin "2") (pinfunction "VOUT_2") (pintype "bidirectional"))
    )
    (net (code "117") (name "VDD") (class "Default")
      (node (ref "C89") (pin "+") (pinfunction "+_+") (pintype "passive"))
      (node (ref "D3") (pin "C") (pinfunction "C_C") (pintype "passive"))
      (node (ref "IC6") (pin "3") (pinfunction "IN_3") (pintype "input"))
      (node (ref "L1") (pin "1") (pinfunction "1_1") (pintype "passive"))
      (node (ref "L3") (pin "1") (pinfunction "1_1") (pintype "passive"))
      (node (ref "SJ1") (pin "1") (pinfunction "1_1") (pintype "passive"))
      (node (ref "SJ2") (pin "1") (pinfunction "1_1") (pintype "passive"))
      (node (ref "SV4") (pin "2") (pinfunction "2_2") (pintype "passive"))
    )
    (net (code "118") (name "unconnected-(IC7B-O-Pad6)") (class "Default")
      (node (ref "IC7") (pin "6") (pinfunction "O_6") (pintype "output"))
    )
    (net (code "119") (name "unconnected-(IC7C-O-Pad8)") (class "Default")
      (node (ref "IC7") (pin "8") (pinfunction "O_8") (pintype "output"))
    )
    (net (code "120") (name "unconnected-(IC7D-O-Pad11)") (class "Default")
      (node (ref "IC7") (pin "11") (pinfunction "O_11") (pintype "output"))
    )
    (net (code "121") (name "unconnected-(U1-INT4X-Pad6)") (class "Default")
      (node (ref "U1") (pin "6") (pinfunction "INT4X_6") (pintype "bidirectional"))
    )
    (net (code "122") (name "unconnected-(U1-ZEROL-Pad22)") (class "Default")
      (node (ref "U1") (pin "22") (pinfunction "ZEROL_22") (pintype "bidirectional"))
    )
    (net (code "123") (name "unconnected-(U1-ZEROR-Pad8)") (class "Default")
      (node (ref "U1") (pin "8") (pinfunction "ZEROR_8") (pintype "bidirectional"))
    )
    (net (code "124") (name "unconnected-(U2-DIN-Pad25)") (class "Default")
      (node (ref "U2") (pin "25") (pinfunction "DIN_25") (pintype "bidirectional"))
    )
    (net (code "125") (name "unconnected-(U2-VINLP-Pad11)") (class "Default")
      (node (ref "U2") (pin "11") (pinfunction "VINLP_11") (pintype "bidirectional"))
    )
    (net (code "126") (name "unconnected-(U2-VINRP-Pad18)") (class "Default")
      (node (ref "U2") (pin "18") (pinfunction "VINRP_18") (pintype "bidirectional"))
    )
    (net (code "127") (name "unconnected-(U7A-#HIB-Pad33)") (class "Default")
      (node (ref "U7") (pin "33") (pinfunction "#HIB_33") (pintype "bidirectional"))
    )
    (net (code "128") (name "unconnected-(U7A-XOSC1-Pad36)") (class "Default")
      (node (ref "U7") (pin "36") (pinfunction "XOSC1_36") (pintype "bidirectional"))
    )
    (net (code "129") (name "unconnected-(U7B-PA7-Pad24)") (class "Default")
      (node (ref "U7") (pin "24") (pinfunction "PA7_24") (pintype "bidirectional"))
    )
    (net (code "130") (name "unconnected-(U7B-PC4-Pad16)") (class "Default")
      (node (ref "U7") (pin "16") (pinfunction "PC4_16") (pintype "bidirectional"))
    )
    (net (code "131") (name "unconnected-(U7B-PC5-Pad15)") (class "Default")
      (node (ref "U7") (pin "15") (pinfunction "PC5_15") (pintype "bidirectional"))
    )
    (net (code "132") (name "unconnected-(U7B-PE0-Pad9)") (class "Default")
      (node (ref "U7") (pin "9") (pinfunction "PE0_9") (pintype "bidirectional"))
    )
    (net (code "133") (name "unconnected-(U7B-PE1-Pad8)") (class "Default")
      (node (ref "U7") (pin "8") (pinfunction "PE1_8") (pintype "bidirectional"))
    )
    (net (code "134") (name "unconnected-(U7B-PE2-Pad7)") (class "Default")
      (node (ref "U7") (pin "7") (pinfunction "PE2_7") (pintype "bidirectional"))
    )
    (net (code "135") (name "unconnected-(U7B-PE3-Pad6)") (class "Default")
      (node (ref "U7") (pin "6") (pinfunction "PE3_6") (pintype "bidirectional"))
    )
    (net (code "136") (name "unconnected-(U7B-PF1-Pad29)") (class "Default")
      (node (ref "U7") (pin "29") (pinfunction "PF1_29") (pintype "bidirectional"))
    )
    (net (code "137") (name "unconnected-(U7B-PF2-Pad30)") (class "Default")
      (node (ref "U7") (pin "30") (pinfunction "PF2_30") (pintype "bidirectional"))
    )
    (net (code "138") (name "unconnected-(X1-GND1-PadM1)") (class "Default")
      (node (ref "X1") (pin "M1") (pinfunction "GND1_M1") (pintype "bidirectional"))
    )
    (net (code "139") (name "unconnected-(X1-GND2-PadM2)") (class "Default")
      (node (ref "X1") (pin "M2") (pinfunction "GND2_M2") (pintype "bidirectional"))
    )
    (net (code "140") (name "unconnected-(X1-GND3-PadM3)") (class "Default")
      (node (ref "X1") (pin "M3") (pinfunction "GND3_M3") (pintype "bidirectional"))
    )
  )
)
